# Mk3_Prototype3.net
KiCad netlist of a schematic drawn in EAGLE
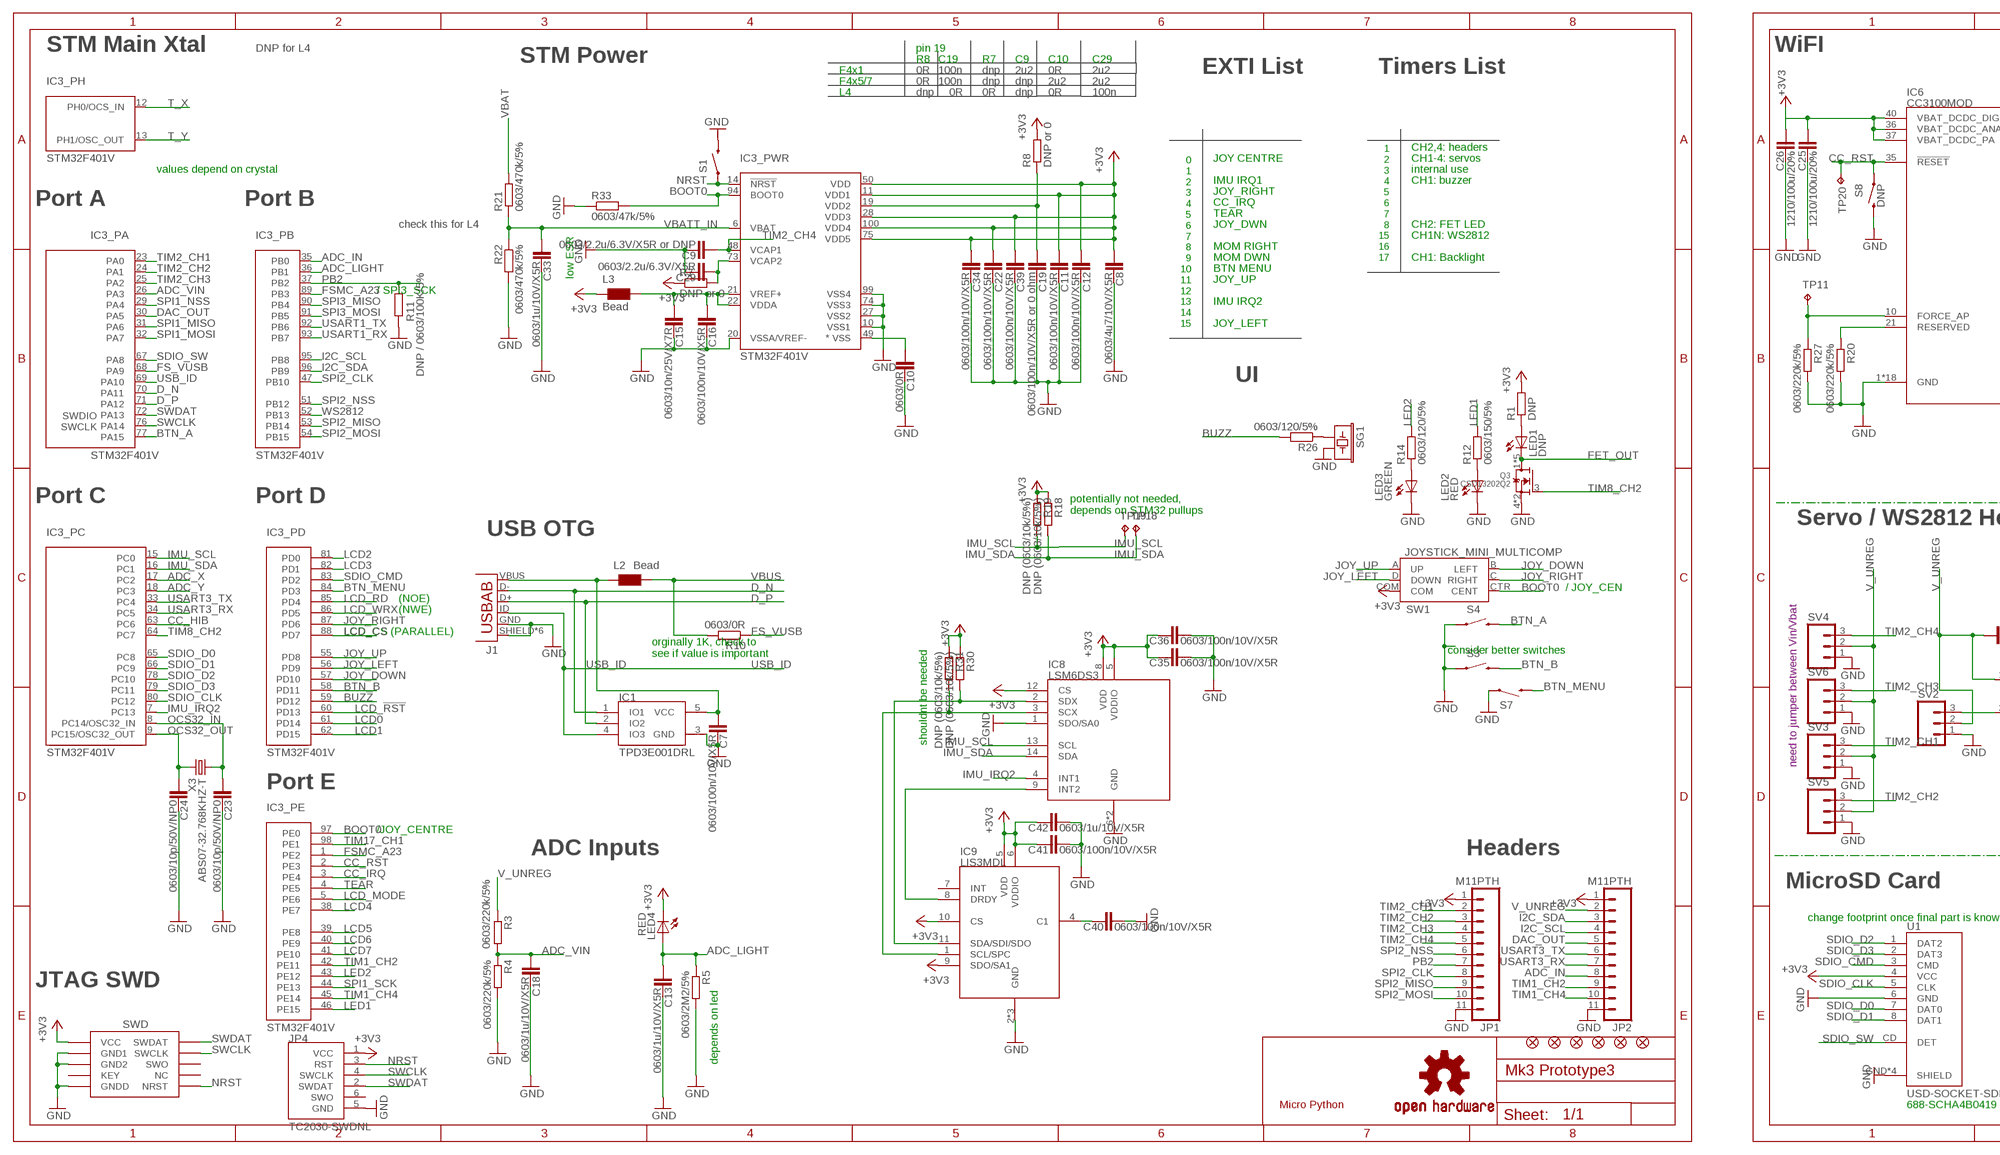
[diagram p0: schematic, sheet 1, part 1 of 2]
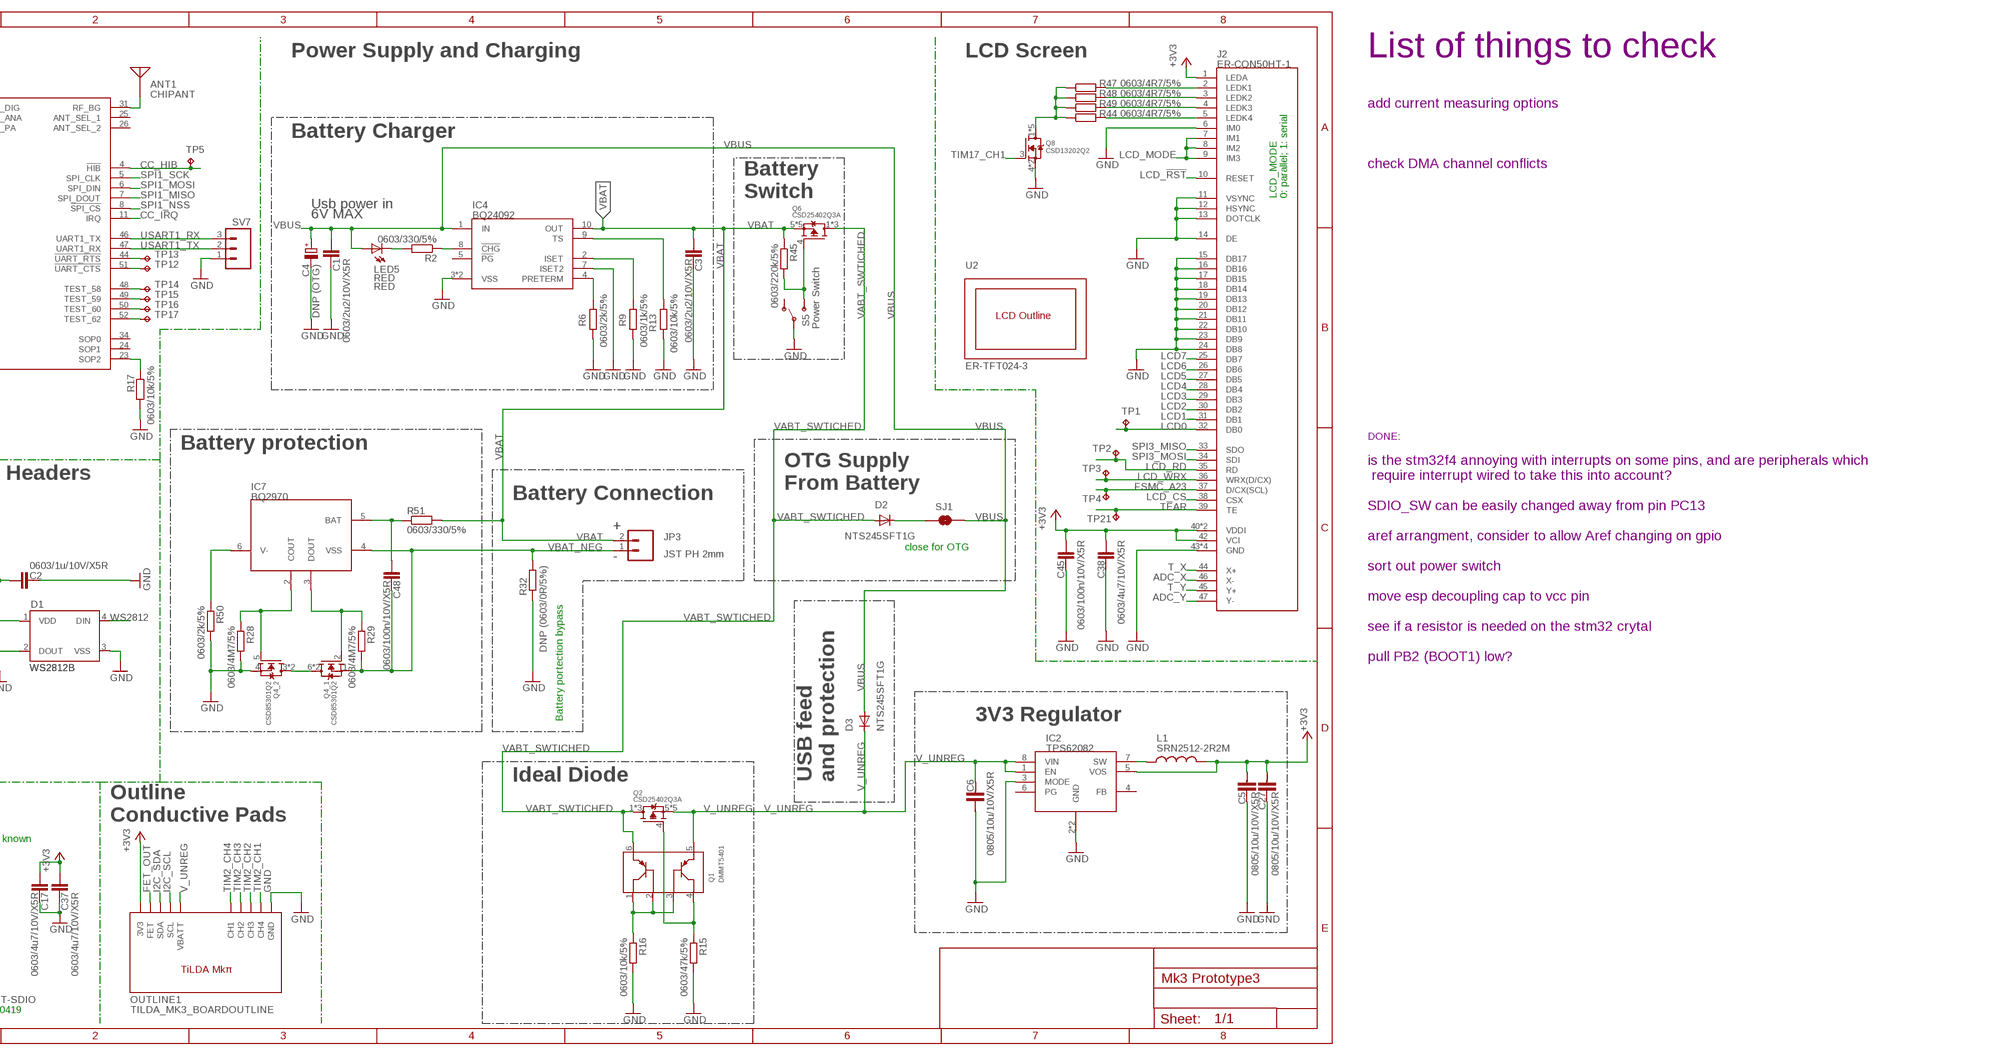
[diagram p1: schematic, sheet 1, part 2 of 2]

(export (version "E")
  (design (tool "Eeschema 10.0.6"))
  (components
    (comp (ref "ANT1")
      (value "CHIPANT")
      (footprint "eagle-import:2450AT42A100")
      (libsource (lib "eagle-import") (part "CHIPANT"))
    )
    (comp (ref "C1")
      (value "0603/2u2/10V/X5R")
      (footprint "eagle-import:C0603K-SMALL")
      (libsource (lib "eagle-import") (part "C-EUC0603K-SMALL"))
    )
    (comp (ref "C2")
      (value "0603/1u/10V/X5R")
      (footprint "eagle-import:C0603K-SMALL")
      (libsource (lib "eagle-import") (part "C-EUC0603K-SMALL"))
    )
    (comp (ref "C3")
      (value "0603/2u2/10V/X5R")
      (footprint "eagle-import:C0603K-SMALL")
      (libsource (lib "eagle-import") (part "C-EUC0603K-SMALL"))
    )
    (comp (ref "C4")
      (value "DNP (OTG)")
      (footprint "eagle-import:E2,5-6")
      (libsource (lib "eagle-import") (part "CPOL-EUE2.5-6"))
    )
    (comp (ref "C5")
      (value "0805/10u/10V/X5R")
      (footprint "eagle-import:C0805-N")
      (libsource (lib "eagle-import") (part "CAPACITOR0805-N"))
    )
    (comp (ref "C6")
      (value "0805/10u/10V/X5R")
      (footprint "eagle-import:C0805-N")
      (libsource (lib "eagle-import") (part "CAPACITOR0805-N"))
    )
    (comp (ref "C7")
      (value "0603/100n/10V/X5R")
      (footprint "eagle-import:C0603K-SMALL")
      (libsource (lib "eagle-import") (part "C-EUC0603K-SMALL"))
    )
    (comp (ref "C8")
      (value "0603/4u7/10V/X5R")
      (footprint "eagle-import:C0603K-SMALL")
      (libsource (lib "eagle-import") (part "C-EUC0603K-SMALL"))
    )
    (comp (ref "C9")
      (value "0603/2.2u/6.3V/X5R or DNP")
      (footprint "eagle-import:C0603K-SMALL")
      (libsource (lib "eagle-import") (part "C-EUC0603K-SMALL"))
    )
    (comp (ref "C10")
      (value "0603/0R")
      (footprint "eagle-import:C0603K-SMALL")
      (libsource (lib "eagle-import") (part "C-EUC0603K-SMALL"))
    )
    (comp (ref "C11")
      (value "0603/100n/10V/X5R")
      (footprint "eagle-import:C0603K-SMALL")
      (libsource (lib "eagle-import") (part "C-EUC0603K-SMALL"))
    )
    (comp (ref "C12")
      (value "0603/100n/10V/X5R")
      (footprint "eagle-import:C0603K-SMALL")
      (libsource (lib "eagle-import") (part "C-EUC0603K-SMALL"))
    )
    (comp (ref "C13")
      (value "0603/1u/10V/X5R")
      (footprint "eagle-import:C0603K-SMALL")
      (libsource (lib "eagle-import") (part "C-EUC0603K-SMALL"))
    )
    (comp (ref "C15")
      (value "0603/10n/25V/X7R")
      (footprint "eagle-import:C0603K-SMALL")
      (libsource (lib "eagle-import") (part "C-EUC0603K-SMALL"))
    )
    (comp (ref "C16")
      (value "0603/100n/10V/X5R")
      (footprint "eagle-import:C0603K-SMALL")
      (libsource (lib "eagle-import") (part "C-EUC0603K-SMALL"))
    )
    (comp (ref "C17")
      (value "0603/4u7/10V/X5R")
      (footprint "eagle-import:C0603K-SMALL")
      (libsource (lib "eagle-import") (part "C-EUC0603K-SMALL"))
    )
    (comp (ref "C18")
      (value "0603/1u/10V/X5R")
      (footprint "eagle-import:C0603K-SMALL")
      (libsource (lib "eagle-import") (part "C-EUC0603K-SMALL"))
    )
    (comp (ref "C19")
      (value "0603/100n/10V/X5R or 0 ohm")
      (footprint "eagle-import:C0603K-SMALL")
      (libsource (lib "eagle-import") (part "C-EUC0603K-SMALL"))
    )
    (comp (ref "C22")
      (value "0603/100n/10V/X5R")
      (footprint "eagle-import:C0603K-SMALL")
      (libsource (lib "eagle-import") (part "C-EUC0603K-SMALL"))
    )
    (comp (ref "C23")
      (value "0603/10p/50V/NP0")
      (footprint "eagle-import:C0603K-SMALL")
      (libsource (lib "eagle-import") (part "C-EUC0603K-SMALL"))
    )
    (comp (ref "C24")
      (value "0603/10p/50V/NP0")
      (footprint "eagle-import:C0603K-SMALL")
      (libsource (lib "eagle-import") (part "C-EUC0603K-SMALL"))
    )
    (comp (ref "C25")
      (value "1210/100u/20%")
      (footprint "eagle-import:C1210K")
      (libsource (lib "eagle-import") (part "C-EUC1210K"))
    )
    (comp (ref "C26")
      (value "1210/100u/20%")
      (footprint "eagle-import:C1210K")
      (libsource (lib "eagle-import") (part "C-EUC1210K"))
    )
    (comp (ref "C27")
      (value "0805/10u/10V/X5R")
      (footprint "eagle-import:C0805-N")
      (libsource (lib "eagle-import") (part "CAPACITOR0805-N"))
    )
    (comp (ref "C29")
      (value "0603/2.2u/6.3V/X5R")
      (footprint "eagle-import:C0603K-SMALL")
      (libsource (lib "eagle-import") (part "C-EUC0603K-SMALL"))
    )
    (comp (ref "C33")
      (value "0603/1u/10V/X5R")
      (footprint "eagle-import:C0603K-SMALL")
      (libsource (lib "eagle-import") (part "C-EUC0603K-SMALL"))
    )
    (comp (ref "C34")
      (value "0603/100n/10V/X5R")
      (footprint "eagle-import:C0603K-SMALL")
      (libsource (lib "eagle-import") (part "C-EUC0603K-SMALL"))
    )
    (comp (ref "C35")
      (value "0603/100n/10V/X5R")
      (footprint "eagle-import:C0603K-SMALL")
      (libsource (lib "eagle-import") (part "C-EUC0603K-SMALL"))
    )
    (comp (ref "C36")
      (value "0603/100n/10V/X5R")
      (footprint "eagle-import:C0603K-SMALL")
      (libsource (lib "eagle-import") (part "C-EUC0603K-SMALL"))
    )
    (comp (ref "C37")
      (value "0603/4u7/10V/X5R")
      (footprint "eagle-import:C0603K-SMALL")
      (libsource (lib "eagle-import") (part "C-EUC0603K-SMALL"))
    )
    (comp (ref "C38")
      (value "0603/4u7/10V/X5R")
      (footprint "eagle-import:C0603K-SMALL")
      (libsource (lib "eagle-import") (part "C-EUC0603K-SMALL"))
    )
    (comp (ref "C39")
      (value "0603/100n/10V/X5R")
      (footprint "eagle-import:C0603K-SMALL")
      (libsource (lib "eagle-import") (part "C-EUC0603K-SMALL"))
    )
    (comp (ref "C40")
      (value "0603/100n/10V/X5R")
      (footprint "eagle-import:C0603K-SMALL")
      (libsource (lib "eagle-import") (part "C-EUC0603K-SMALL"))
    )
    (comp (ref "C41")
      (value "0603/100n/10V/X5R")
      (footprint "eagle-import:C0603K-SMALL")
      (libsource (lib "eagle-import") (part "C-EUC0603K-SMALL"))
    )
    (comp (ref "C42")
      (value "0603/1u/10V/X5R")
      (footprint "eagle-import:C0603K-SMALL")
      (libsource (lib "eagle-import") (part "C-EUC0603K-SMALL"))
    )
    (comp (ref "C45")
      (value "0603/100n/10V/X5R")
      (footprint "eagle-import:C0603K-SMALL")
      (libsource (lib "eagle-import") (part "C-EUC0603K-SMALL"))
    )
    (comp (ref "C48")
      (value "0603/100n/10V/X5R")
      (footprint "eagle-import:C0603K-SMALL")
      (libsource (lib "eagle-import") (part "C-EUC0603K-SMALL"))
    )
    (comp (ref "D1")
      (value "WS2812B")
      (footprint "eagle-import:WS2812B")
      (libsource (lib "eagle-import") (part "WS2812B"))
    )
    (comp (ref "D2")
      (value "NTS245SFT1G")
      (footprint "eagle-import:SOD123")
      (libsource (lib "eagle-import") (part "1N4148-SOD123"))
    )
    (comp (ref "D3")
      (value "NTS245SFT1G")
      (footprint "eagle-import:SOD123")
      (libsource (lib "eagle-import") (part "1N4148-SOD123"))
    )
    (comp (ref "FID1")
      (value "FIDUCIAL1X2.5-STOP")
      (footprint "eagle-import:FIDUCIAL-1X2.5-STOP")
      (libsource (lib "eagle-import") (part "FIDUCIAL1X2.5-STOP"))
    )
    (comp (ref "FID2")
      (value "FIDUCIAL1X2.5-STOP")
      (footprint "eagle-import:FIDUCIAL-1X2.5-STOP")
      (libsource (lib "eagle-import") (part "FIDUCIAL1X2.5-STOP"))
    )
    (comp (ref "FID3")
      (value "FIDUCIAL1X2.5-STOP")
      (footprint "eagle-import:FIDUCIAL-1X2.5-STOP")
      (libsource (lib "eagle-import") (part "FIDUCIAL1X2.5-STOP"))
    )
    (comp (ref "FID4")
      (value "FIDUCIAL1X2.5-STOP")
      (footprint "eagle-import:FIDUCIAL-1X2.5-STOP")
      (libsource (lib "eagle-import") (part "FIDUCIAL1X2.5-STOP"))
    )
    (comp (ref "FID5")
      (value "FIDUCIAL1X2.5-STOP")
      (footprint "eagle-import:FIDUCIAL-1X2.5-STOP")
      (libsource (lib "eagle-import") (part "FIDUCIAL1X2.5-STOP"))
    )
    (comp (ref "FID6")
      (value "FIDUCIAL1X2.5-STOP")
      (footprint "eagle-import:FIDUCIAL-1X2.5-STOP")
      (libsource (lib "eagle-import") (part "FIDUCIAL1X2.5-STOP"))
    )
    (comp (ref "IC1")
      (value "TPD3E001DRL")
      (footprint "eagle-import:DRL-5")
      (libsource (lib "eagle-import") (part "TPD3E001DRL"))
    )
    (comp (ref "IC2")
      (value "TPS62082")
      (footprint "eagle-import:WSON8")
      (libsource (lib "eagle-import") (part "TPS62082"))
    )
    (comp (ref "IC3")
      (value "STM32F401V")
      (footprint "eagle-import:TQFP100")
      (fields (field (name "FARNELL") "2432116"))
      (libsource (lib "eagle-import") (part "STM32F401V"))
    )
    (comp (ref "IC4")
      (value "BQ24092")
      (footprint "eagle-import:HVSSOP10")
      (libsource (lib "eagle-import") (part "BQ2409X"))
    )
    (comp (ref "IC6")
      (value "CC3100MOD")
      (footprint "eagle-import:CC3100MOD")
      (libsource (lib "eagle-import") (part "CC3100MOD"))
    )
    (comp (ref "IC7")
      (value "BQ2970")
      (footprint "eagle-import:WSON-6")
      (libsource (lib "eagle-import") (part "BQ2970"))
    )
    (comp (ref "IC8")
      (value "LSM6DS3")
      (footprint "eagle-import:LGA14")
      (libsource (lib "eagle-import") (part "LSM6DS3"))
    )
    (comp (ref "IC9")
      (value "LIS3MDL")
      (footprint "eagle-import:LGA12")
      (libsource (lib "eagle-import") (part "LIS3MDL"))
    )
    (comp (ref "J1")
      (value "ZX62-AB-5PA(11)")
      (footprint "eagle-import:USB-AB-MICRO-SMD_LWK")
      (libsource (lib "eagle-import") (part "USB-AB-LWK"))
    )
    (comp (ref "J2")
      (value "ER-CON50HT-1")
      (footprint "eagle-import:FH12-50S-0.5SH")
      (libsource (lib "eagle-import") (part "ER-TFT024-3"))
    )
    (comp (ref "J3")
      (value "SWD_SHROUD-PINHEAD")
      (footprint "eagle-import:PINHEAD_2X05_127")
      (libsource (lib "eagle-import") (part "SWD_SHROUD-PINHEAD"))
    )
    (comp (ref "JP1")
      (value "M11PTH")
      (footprint "eagle-import:1X11")
      (libsource (lib "eagle-import") (part "M11PTH"))
    )
    (comp (ref "JP2")
      (value "M11PTH")
      (footprint "eagle-import:1X11")
      (libsource (lib "eagle-import") (part "M11PTH"))
    )
    (comp (ref "JP3")
      (value "JST PH 2mm")
      (footprint "eagle-import:JST-2-SMD")
      (libsource (lib "eagle-import") (part "M02-JST-2MM-SMT"))
    )
    (comp (ref "JP4")
      (value "TC2030-SWDNL")
      (footprint "eagle-import:TC2030-MCP-NL")
      (libsource (lib "eagle-import") (part "TC2030-SWDNL"))
    )
    (comp (ref "L1")
      (value "SRN2512-2R2M")
      (footprint "eagle-import:1008")
      (libsource (lib "eagle-import") (part "INDUCTOR1008"))
    )
    (comp (ref "L2")
      (value "Bead")
      (footprint "eagle-import:WUERTH-0805")
      (libsource (lib "eagle-import") (part "WE-CBF_0805"))
    )
    (comp (ref "L3")
      (value "Bead")
      (footprint "eagle-import:WUERTH-0805")
      (libsource (lib "eagle-import") (part "WE-CBF_0805"))
    )
    (comp (ref "LED1")
      (value "DNP")
      (footprint "eagle-import:LED5MM")
      (libsource (lib "eagle-import") (part "LED5MM"))
    )
    (comp (ref "LED2")
      (value "RED")
      (footprint "eagle-import:LED-0603-CORRECT")
      (fields (field (name "COLOUR") "RED"))
      (libsource (lib "eagle-import") (part "LED0603-CORRECT"))
    )
    (comp (ref "LED3")
      (value "GREEN")
      (footprint "eagle-import:LED-0603-CORRECT")
      (fields (field (name "COLOUR") "GREEN"))
      (libsource (lib "eagle-import") (part "LED0603-CORRECT"))
    )
    (comp (ref "LED4")
      (value "RED")
      (footprint "eagle-import:LED-0603-CORRECT")
      (libsource (lib "eagle-import") (part "LED0603-CORRECT"))
    )
    (comp (ref "LED5")
      (value "RED")
      (footprint "eagle-import:LED-0603-CORRECT")
      (fields (field (name "COLOUR") "RED"))
      (libsource (lib "eagle-import") (part "LED0603-CORRECT"))
    )
    (comp (ref "LOGO1")
      (value "OSHW-LOGOM")
      (footprint "eagle-import:OSHW-LOGO-M")
      (libsource (lib "eagle-import") (part "OSHW-LOGOM"))
    )
    (comp (ref "LOGO3")
      (value "MICROPYTHON-STOP")
      (footprint "eagle-import:UPYTHON_LOGO_STOPONLY")
      (libsource (lib "eagle-import") (part "MICROPYTHON-STOP"))
    )
    (comp (ref "OUTLINE1")
      (value "TILDA_MK3_BOARDOUTLINE")
      (footprint "eagle-import:TILDA_MKE_OUTLINE")
      (libsource (lib "eagle-import") (part "TILDA_MK3_BOARDOUTLINE"))
    )
    (comp (ref "Q1")
      (value "DMMT5401")
      (footprint "eagle-import:SOT26")
      (libsource (lib "eagle-import") (part "DMMT5401"))
    )
    (comp (ref "Q2")
      (value "CSD25402Q3A")
      (footprint "eagle-import:Q3A")
      (libsource (lib "eagle-import") (part "CSD25402Q3A"))
    )
    (comp (ref "Q3")
      (value "CSD13202Q2")
      (footprint "eagle-import:Q2")
      (libsource (lib "eagle-import") (part "CSD13202Q2"))
    )
    (comp (ref "Q4")
      (value "CSD85301Q2")
      (footprint "eagle-import:Q2_DUAL")
      (fields (field (name "FARNELL") "2470183"))
      (libsource (lib "eagle-import") (part "CSD85301Q2"))
    )
    (comp (ref "Q6")
      (value "CSD25402Q3A")
      (footprint "eagle-import:Q3A")
      (libsource (lib "eagle-import") (part "CSD25402Q3A"))
    )
    (comp (ref "Q8")
      (value "CSD13202Q2")
      (footprint "eagle-import:Q2")
      (libsource (lib "eagle-import") (part "CSD13202Q2"))
    )
    (comp (ref "R1")
      (value "DNP")
      (footprint "eagle-import:0207_10")
      (libsource (lib "eagle-import") (part "R-EU_0207/10"))
    )
    (comp (ref "R2")
      (value "0603/330/5%")
      (footprint "eagle-import:C0603K-SMALL")
      (libsource (lib "eagle-import") (part "R-EU_0603K-SMALL"))
    )
    (comp (ref "R3")
      (value "0603/220k/5%")
      (footprint "eagle-import:C0603K-SMALL")
      (libsource (lib "eagle-import") (part "R-EU_0603K-SMALL"))
    )
    (comp (ref "R4")
      (value "0603/220k/5%")
      (footprint "eagle-import:C0603K-SMALL")
      (libsource (lib "eagle-import") (part "R-EU_0603K-SMALL"))
    )
    (comp (ref "R5")
      (value "0603/2M2/5%")
      (footprint "eagle-import:C0603K-SMALL")
      (libsource (lib "eagle-import") (part "R-EU_0603K-SMALL"))
    )
    (comp (ref "R6")
      (value "0603/2k/5%")
      (footprint "eagle-import:C0603K-SMALL")
      (libsource (lib "eagle-import") (part "R-EU_0603K-SMALL"))
    )
    (comp (ref "R7")
      (value "DNP or 0")
      (footprint "eagle-import:C0603K-SMALL")
      (libsource (lib "eagle-import") (part "R-EU_0603K-SMALL"))
    )
    (comp (ref "R8")
      (value "DNP or 0")
      (footprint "eagle-import:C0603K-SMALL")
      (libsource (lib "eagle-import") (part "R-EU_0603K-SMALL"))
    )
    (comp (ref "R9")
      (value "0603/1k/5%")
      (footprint "eagle-import:C0603K-SMALL")
      (libsource (lib "eagle-import") (part "R-EU_0603K-SMALL"))
    )
    (comp (ref "R10")
      (value "0603/0R")
      (footprint "eagle-import:C0603K-SMALL")
      (libsource (lib "eagle-import") (part "R-EU_0603K-SMALL"))
    )
    (comp (ref "R11")
      (value "DNP / 0603/100K/5%")
      (footprint "eagle-import:C0603K-SMALL")
      (libsource (lib "eagle-import") (part "R-EU_0603K-SMALL"))
    )
    (comp (ref "R12")
      (value "0603/150/5%")
      (footprint "eagle-import:C0603K-SMALL")
      (libsource (lib "eagle-import") (part "R-EU_0603K-SMALL"))
    )
    (comp (ref "R13")
      (value "0603/10k/5%")
      (footprint "eagle-import:C0603K-SMALL")
      (libsource (lib "eagle-import") (part "R-EU_0603K-SMALL"))
    )
    (comp (ref "R14")
      (value "0603/120/5%")
      (footprint "eagle-import:C0603K-SMALL")
      (libsource (lib "eagle-import") (part "R-EU_0603K-SMALL"))
    )
    (comp (ref "R15")
      (value "0603/47k/5%")
      (footprint "eagle-import:C0603K-SMALL")
      (libsource (lib "eagle-import") (part "R-EU_0603K-SMALL"))
    )
    (comp (ref "R16")
      (value "0603/10k/5%")
      (footprint "eagle-import:C0603K-SMALL")
      (libsource (lib "eagle-import") (part "R-EU_0603K-SMALL"))
    )
    (comp (ref "R17")
      (value "0603/10k/5%")
      (footprint "eagle-import:C0603K-SMALL")
      (libsource (lib "eagle-import") (part "R-EU_0603K-SMALL"))
    )
    (comp (ref "R18")
      (value "DNP (0603/10k/5%)")
      (footprint "eagle-import:C0603K-SMALL")
      (libsource (lib "eagle-import") (part "R-EU_0603K-SMALL"))
    )
    (comp (ref "R19")
      (value "DNP (0603/10k/5%)")
      (footprint "eagle-import:C0603K-SMALL")
      (libsource (lib "eagle-import") (part "R-EU_0603K-SMALL"))
    )
    (comp (ref "R20")
      (value "0603/220k/5%")
      (footprint "eagle-import:C0603K-SMALL")
      (libsource (lib "eagle-import") (part "R-EU_0603K-SMALL"))
    )
    (comp (ref "R21")
      (value "0603/470k/5%")
      (footprint "eagle-import:C0603K-SMALL")
      (libsource (lib "eagle-import") (part "R-EU_0603K-SMALL"))
    )
    (comp (ref "R22")
      (value "0603/470k/5%")
      (footprint "eagle-import:C0603K-SMALL")
      (libsource (lib "eagle-import") (part "R-EU_0603K-SMALL"))
    )
    (comp (ref "R26")
      (value "0603/120/5%")
      (footprint "eagle-import:C0603K-SMALL")
      (libsource (lib "eagle-import") (part "R-EU_0603K-SMALL"))
    )
    (comp (ref "R27")
      (value "0603/220k/5%")
      (footprint "eagle-import:C0603K-SMALL")
      (libsource (lib "eagle-import") (part "R-EU_0603K-SMALL"))
    )
    (comp (ref "R28")
      (value "0603/4M7/5%")
      (footprint "eagle-import:C0603K-SMALL")
      (libsource (lib "eagle-import") (part "R-EU_0603K-SMALL"))
    )
    (comp (ref "R29")
      (value "0603/4M7/5%")
      (footprint "eagle-import:C0603K-SMALL")
      (libsource (lib "eagle-import") (part "R-EU_0603K-SMALL"))
    )
    (comp (ref "R30")
      (value "DNP (0603/10k/5%)")
      (footprint "eagle-import:C0603K-SMALL")
      (libsource (lib "eagle-import") (part "R-EU_0603K-SMALL"))
    )
    (comp (ref "R31")
      (value "DNP (0603/10k/5%)")
      (footprint "eagle-import:C0603K-SMALL")
      (libsource (lib "eagle-import") (part "R-EU_0603K-SMALL"))
    )
    (comp (ref "R32")
      (value "DNP (0603/0R/5%)")
      (footprint "eagle-import:C0603K-SMALL")
      (libsource (lib "eagle-import") (part "R-EU_0603K-SMALL"))
    )
    (comp (ref "R33")
      (value "0603/47k/5%")
      (footprint "eagle-import:C0603K-SMALL")
      (libsource (lib "eagle-import") (part "R-EU_0603K-SMALL"))
    )
    (comp (ref "R44")
      (value "0603/4R7/5%")
      (footprint "eagle-import:C0603K-SMALL")
      (libsource (lib "eagle-import") (part "R-EU_0603K-SMALL"))
    )
    (comp (ref "R45")
      (value "0603/220k/5%")
      (footprint "eagle-import:C0603K-SMALL")
      (libsource (lib "eagle-import") (part "R-EU_0603K-SMALL"))
    )
    (comp (ref "R47")
      (value "0603/4R7/5%")
      (footprint "eagle-import:C0603K-SMALL")
      (libsource (lib "eagle-import") (part "R-EU_0603K-SMALL"))
    )
    (comp (ref "R48")
      (value "0603/4R7/5%")
      (footprint "eagle-import:C0603K-SMALL")
      (libsource (lib "eagle-import") (part "R-EU_0603K-SMALL"))
    )
    (comp (ref "R49")
      (value "0603/4R7/5%")
      (footprint "eagle-import:C0603K-SMALL")
      (libsource (lib "eagle-import") (part "R-EU_0603K-SMALL"))
    )
    (comp (ref "R50")
      (value "0603/2k/5%")
      (footprint "eagle-import:C0603K-SMALL")
      (libsource (lib "eagle-import") (part "R-EU_0603K-SMALL"))
    )
    (comp (ref "R51")
      (value "0603/330/5%")
      (footprint "eagle-import:C0603K-SMALL")
      (libsource (lib "eagle-import") (part "R-EU_0603K-SMALL"))
    )
    (comp (ref "S1")
      (value "SWITCH-MOMENTARY-2SMD-1101NE")
      (footprint "eagle-import:TACTILE-SWITCH-1101NE")
      (libsource (lib "eagle-import") (part "SWITCH-MOMENTARY-2SMD-1101NE"))
    )
    (comp (ref "S3")
      (value "1217769")
      (footprint "eagle-import:SKPMAPE010-COMBINED")
      (libsource (lib "eagle-import") (part "SWITCH-MOMENTARY-2-SKPMAPE010-COMBINED"))
    )
    (comp (ref "S4")
      (value "1217769")
      (footprint "eagle-import:SKPMAPE010-COMBINED")
      (libsource (lib "eagle-import") (part "SWITCH-MOMENTARY-2-SKPMAPE010-COMBINED"))
    )
    (comp (ref "S5")
      (value "Power Switch")
      (footprint "eagle-import:SWITCH-SPST-SMD-A")
      (libsource (lib "eagle-import") (part "SWITCH-SPST-SMD-A"))
    )
    (comp (ref "S7")
      (value "SWITCH-MOMENTARY-2SMD-1101NE")
      (footprint "eagle-import:TACTILE-SWITCH-1101NE")
      (libsource (lib "eagle-import") (part "SWITCH-MOMENTARY-2SMD-1101NE"))
    )
    (comp (ref "S8")
      (value "DNP")
      (footprint "eagle-import:TACTILE-SWITCH-1101NE")
      (libsource (lib "eagle-import") (part "SWITCH-MOMENTARY-2SMD-1101NE"))
    )
    (comp (ref "SG1")
      (value "BUZZER-PKLCS1212E")
      (footprint "eagle-import:BUZZER-PKLCS1212E")
      (libsource (lib "eagle-import") (part "BUZZER-PKLCS1212E"))
    )
    (comp (ref "SJ1")
      (value "JUMPER-PAD-2-NOYES_SILK")
      (footprint "eagle-import:PAD-JUMPER-2-NO_YES_SILK")
      (libsource (lib "eagle-import") (part "JUMPER-PAD-2-NOYES_SILK"))
    )
    (comp (ref "SV2")
      (value "M03PTH")
      (footprint "eagle-import:1X03")
      (libsource (lib "eagle-import") (part "M03PTH"))
    )
    (comp (ref "SV3")
      (value "M03PTH")
      (footprint "eagle-import:1X03")
      (libsource (lib "eagle-import") (part "M03PTH"))
    )
    (comp (ref "SV4")
      (value "M03PTH")
      (footprint "eagle-import:1X03")
      (libsource (lib "eagle-import") (part "M03PTH"))
    )
    (comp (ref "SV5")
      (value "M03PTH")
      (footprint "eagle-import:1X03")
      (libsource (lib "eagle-import") (part "M03PTH"))
    )
    (comp (ref "SV6")
      (value "M03PTH")
      (footprint "eagle-import:1X03")
      (libsource (lib "eagle-import") (part "M03PTH"))
    )
    (comp (ref "SV7")
      (value "M03PTH")
      (footprint "eagle-import:1X03")
      (libsource (lib "eagle-import") (part "M03PTH"))
    )
    (comp (ref "SW1")
      (value "JOYSTICK_MINI_MULTICOMP")
      (footprint "eagle-import:JOYSTICK_MULTICOMP")
      (libsource (lib "eagle-import") (part "JOYSTICK_MINI_MULTICOMP"))
    )
    (comp (ref "TP1")
      (value "TPB1,27")
      (footprint "eagle-import:B1,27")
      (libsource (lib "eagle-import") (part "TPB1,27"))
    )
    (comp (ref "TP2")
      (value "TPB1,27")
      (footprint "eagle-import:B1,27")
      (libsource (lib "eagle-import") (part "TPB1,27"))
    )
    (comp (ref "TP3")
      (value "TPB1,27")
      (footprint "eagle-import:B1,27")
      (libsource (lib "eagle-import") (part "TPB1,27"))
    )
    (comp (ref "TP4")
      (value "TPB1,27")
      (footprint "eagle-import:B1,27")
      (libsource (lib "eagle-import") (part "TPB1,27"))
    )
    (comp (ref "TP5")
      (value "TPB1,27")
      (footprint "eagle-import:B1,27")
      (libsource (lib "eagle-import") (part "TPB1,27"))
    )
    (comp (ref "TP11")
      (value "TPB1,27")
      (footprint "eagle-import:B1,27")
      (libsource (lib "eagle-import") (part "TPB1,27"))
    )
    (comp (ref "TP12")
      (value "TPB1,27")
      (footprint "eagle-import:B1,27")
      (libsource (lib "eagle-import") (part "TPB1,27"))
    )
    (comp (ref "TP13")
      (value "TPB1,27")
      (footprint "eagle-import:B1,27")
      (libsource (lib "eagle-import") (part "TPB1,27"))
    )
    (comp (ref "TP14")
      (value "TPB1,27")
      (footprint "eagle-import:B1,27")
      (libsource (lib "eagle-import") (part "TPB1,27"))
    )
    (comp (ref "TP15")
      (value "TPB1,27")
      (footprint "eagle-import:B1,27")
      (libsource (lib "eagle-import") (part "TPB1,27"))
    )
    (comp (ref "TP16")
      (value "TPB1,27")
      (footprint "eagle-import:B1,27")
      (libsource (lib "eagle-import") (part "TPB1,27"))
    )
    (comp (ref "TP17")
      (value "TPB1,27")
      (footprint "eagle-import:B1,27")
      (libsource (lib "eagle-import") (part "TPB1,27"))
    )
    (comp (ref "TP18")
      (value "TPB1,27")
      (footprint "eagle-import:B1,27")
      (libsource (lib "eagle-import") (part "TPB1,27"))
    )
    (comp (ref "TP19")
      (value "TPB1,27")
      (footprint "eagle-import:B1,27")
      (libsource (lib "eagle-import") (part "TPB1,27"))
    )
    (comp (ref "TP20")
      (value "TPB1,27")
      (footprint "eagle-import:B1,27")
      (libsource (lib "eagle-import") (part "TPB1,27"))
    )
    (comp (ref "TP21")
      (value "TPB1,27")
      (footprint "eagle-import:B1,27")
      (libsource (lib "eagle-import") (part "TPB1,27"))
    )
    (comp (ref "U1")
      (value "USD-SOCKET-SDIO")
      (footprint "eagle-import:0011XAAX09X")
      (libsource (lib "eagle-import") (part "USD-SOCKET-SDIO"))
    )
    (comp (ref "U2")
      (value "ER-TFT024-3")
      (footprint "eagle-import:ER-TFT024-3")
      (libsource (lib "eagle-import") (part "ER-TFT024-3-OUTLINE"))
    )
    (comp (ref "X3")
      (value "ABS07-32.768KHZ-T")
      (footprint "eagle-import:RESONATOR_EPSON_FC_145")
      (libsource (lib "eagle-import") (part "RESONATOR_EPSON_FC_145"))
    )
  )
  (nets
    (net (code "1") (name "+3V3") (class "Default")
      (node (ref "C11") (pin "2") (pinfunction "2_2") (pintype "passive"))
      (node (ref "C12") (pin "2") (pinfunction "2_2") (pintype "passive"))
      (node (ref "C17") (pin "2") (pinfunction "2_2") (pintype "passive"))
      (node (ref "C22") (pin "2") (pinfunction "2_2") (pintype "passive"))
      (node (ref "C25") (pin "1") (pinfunction "1_1") (pintype "passive"))
      (node (ref "C26") (pin "1") (pinfunction "1_1") (pintype "passive"))
      (node (ref "C27") (pin "1") (pinfunction "1_1") (pintype "passive"))
      (node (ref "C34") (pin "2") (pinfunction "2_2") (pintype "passive"))
      (node (ref "C35") (pin "1") (pinfunction "1_1") (pintype "passive"))
      (node (ref "C36") (pin "1") (pinfunction "1_1") (pintype "passive"))
      (node (ref "C37") (pin "2") (pinfunction "2_2") (pintype "passive"))
      (node (ref "C38") (pin "2") (pinfunction "2_2") (pintype "passive"))
      (node (ref "C39") (pin "2") (pinfunction "2_2") (pintype "passive"))
      (node (ref "C41") (pin "1") (pinfunction "1_1") (pintype "passive"))
      (node (ref "C42") (pin "1") (pinfunction "1_1") (pintype "passive"))
      (node (ref "C45") (pin "2") (pinfunction "2_2") (pintype "passive"))
      (node (ref "C5") (pin "1") (pinfunction "1_1") (pintype "passive"))
      (node (ref "C8") (pin "2") (pinfunction "2_2") (pintype "passive"))
      (node (ref "IC2") (pin "5") (pinfunction "VOS_5") (pintype "input"))
      (node (ref "IC3") (pin "100") (pinfunction "VDD4_100") (pintype "bidirectional"))
      (node (ref "IC3") (pin "11") (pinfunction "VDD1_11") (pintype "bidirectional"))
      (node (ref "IC3") (pin "28") (pinfunction "VDD3_28") (pintype "bidirectional"))
      (node (ref "IC3") (pin "50") (pinfunction "VDD_50") (pintype "bidirectional"))
      (node (ref "IC3") (pin "75") (pinfunction "VDD5_75") (pintype "bidirectional"))
      (node (ref "IC6") (pin "36") (pinfunction "VBAT_DCDC_ANA_36") (pintype "power_in"))
      (node (ref "IC6") (pin "37") (pinfunction "VBAT_DCDC_PA_37") (pintype "power_in"))
      (node (ref "IC6") (pin "40") (pinfunction "VBAT_DCDC_DIG_40") (pintype "power_in"))
      (node (ref "IC8") (pin "12") (pinfunction "CS_12") (pintype "input"))
      (node (ref "IC8") (pin "5") (pinfunction "VDDIO_5") (pintype "power_in"))
      (node (ref "IC8") (pin "8") (pinfunction "VDD_8") (pintype "power_in"))
      (node (ref "IC9") (pin "10") (pinfunction "CS_10") (pintype "input"))
      (node (ref "IC9") (pin "5") (pinfunction "VDD_5") (pintype "power_in"))
      (node (ref "IC9") (pin "6") (pinfunction "VDDIO_6") (pintype "power_in"))
      (node (ref "IC9") (pin "9") (pinfunction "SDO/SA1_9") (pintype "bidirectional"))
      (node (ref "J2") (pin "1") (pinfunction "LEDA_1") (pintype "passive"))
      (node (ref "J2") (pin "40") (pinfunction "VDDI_40") (pintype "power_in"))
      (node (ref "J2") (pin "41") (pinfunction "VDDI_41") (pintype "power_in"))
      (node (ref "J2") (pin "42") (pinfunction "VCI_42") (pintype "power_in"))
      (node (ref "J3") (pin "1") (pinfunction "VCC_1") (pintype "power_in"))
      (node (ref "JP1") (pin "1") (pinfunction "1_1") (pintype "passive"))
      (node (ref "JP2") (pin "1") (pinfunction "1_1") (pintype "passive"))
      (node (ref "JP4") (pin "1") (pinfunction "VCC_1") (pintype "power_in"))
      (node (ref "L1") (pin "2") (pinfunction "2_2") (pintype "passive"))
      (node (ref "L3") (pin "1") (pinfunction "1_1") (pintype "passive"))
      (node (ref "LED4") (pin "C") (pinfunction "C_C") (pintype "passive"))
      (node (ref "OUTLINE1") (pin "3V3") (pinfunction "3V3_3V3") (pintype "bidirectional"))
      (node (ref "R1") (pin "2") (pinfunction "2_2") (pintype "passive"))
      (node (ref "R18") (pin "1") (pinfunction "1_1") (pintype "passive"))
      (node (ref "R19") (pin "1") (pinfunction "1_1") (pintype "passive"))
      (node (ref "R30") (pin "1") (pinfunction "1_1") (pintype "passive"))
      (node (ref "R31") (pin "1") (pinfunction "1_1") (pintype "passive"))
      (node (ref "R7") (pin "1") (pinfunction "1_1") (pintype "passive"))
      (node (ref "R8") (pin "2") (pinfunction "2_2") (pintype "passive"))
      (node (ref "SW1") (pin "COM") (pinfunction "COM_COM") (pintype "bidirectional"))
      (node (ref "U1") (pin "4") (pinfunction "VCC_4") (pintype "bidirectional"))
    )
    (net (code "2") (name "/ADC_IN") (class "Default")
      (node (ref "IC3") (pin "35") (pinfunction "PB0_35") (pintype "bidirectional"))
      (node (ref "JP2") (pin "8") (pinfunction "8_8") (pintype "passive"))
    )
    (net (code "3") (name "/ADC_LIGHT") (class "Default")
      (node (ref "C13") (pin "2") (pinfunction "2_2") (pintype "passive"))
      (node (ref "IC3") (pin "36") (pinfunction "PB1_36") (pintype "bidirectional"))
      (node (ref "LED4") (pin "A") (pinfunction "A_A") (pintype "passive"))
      (node (ref "R5") (pin "1") (pinfunction "1_1") (pintype "passive"))
    )
    (net (code "4") (name "/ADC_VIN") (class "Default")
      (node (ref "C18") (pin "2") (pinfunction "2_2") (pintype "passive"))
      (node (ref "IC3") (pin "26") (pinfunction "PA3_26") (pintype "bidirectional"))
      (node (ref "R3") (pin "2") (pinfunction "2_2") (pintype "passive"))
      (node (ref "R4") (pin "1") (pinfunction "1_1") (pintype "passive"))
    )
    (net (code "5") (name "/ADC_X") (class "Default")
      (node (ref "IC3") (pin "17") (pinfunction "PC2_17") (pintype "bidirectional"))
      (node (ref "J2") (pin "46") (pinfunction "X-_46") (pintype "passive"))
    )
    (net (code "6") (name "/ADC_Y") (class "Default")
      (node (ref "IC3") (pin "18") (pinfunction "PC3_18") (pintype "bidirectional"))
      (node (ref "J2") (pin "47") (pinfunction "Y-_47") (pintype "passive"))
    )
    (net (code "7") (name "/BOOT0") (class "Default")
      (node (ref "IC3") (pin "94") (pinfunction "BOOT0_94") (pintype "bidirectional"))
      (node (ref "IC3") (pin "97") (pinfunction "PE0_97") (pintype "bidirectional"))
      (node (ref "R33") (pin "2") (pinfunction "2_2") (pintype "passive"))
      (node (ref "SW1") (pin "CTR") (pinfunction "CENT_CTR") (pintype "bidirectional"))
    )
    (net (code "8") (name "/BTN_A") (class "Default")
      (node (ref "IC3") (pin "77") (pinfunction "PA15_77") (pintype "bidirectional"))
      (node (ref "S4") (pin "2") (pinfunction "2_2") (pintype "passive"))
      (node (ref "S4") (pin "B1") (pinfunction "2_B1") (pintype "passive"))
      (node (ref "S4") (pin "B2") (pinfunction "2_B2") (pintype "passive"))
    )
    (net (code "9") (name "/BTN_B") (class "Default")
      (node (ref "IC3") (pin "58") (pinfunction "PD11_58") (pintype "bidirectional"))
      (node (ref "S3") (pin "2") (pinfunction "2_2") (pintype "passive"))
      (node (ref "S3") (pin "B1") (pinfunction "2_B1") (pintype "passive"))
      (node (ref "S3") (pin "B2") (pinfunction "2_B2") (pintype "passive"))
    )
    (net (code "10") (name "/BTN_MENU") (class "Default")
      (node (ref "IC3") (pin "84") (pinfunction "PD3_84") (pintype "bidirectional"))
      (node (ref "S7") (pin "2") (pinfunction "2_2") (pintype "passive"))
    )
    (net (code "11") (name "/BUZZ") (class "Default")
      (node (ref "IC3") (pin "59") (pinfunction "PD12_59") (pintype "bidirectional"))
      (node (ref "R26") (pin "2") (pinfunction "2_2") (pintype "passive"))
    )
    (net (code "12") (name "/CC_HIB") (class "Default")
      (node (ref "IC3") (pin "63") (pinfunction "PC6_63") (pintype "bidirectional"))
      (node (ref "IC6") (pin "4") (pinfunction "~{HIB}_4") (pintype "input"))
      (node (ref "TP5") (pin "TP") (pinfunction "TP_TP") (pintype "input"))
    )
    (net (code "13") (name "/CC_IRQ") (class "Default")
      (node (ref "IC3") (pin "3") (pinfunction "PE4_3") (pintype "bidirectional"))
      (node (ref "IC6") (pin "11") (pinfunction "IRQ_11") (pintype "output"))
    )
    (net (code "14") (name "/CC_RST") (class "Default")
      (node (ref "IC3") (pin "2") (pinfunction "PE3_2") (pintype "bidirectional"))
      (node (ref "IC6") (pin "35") (pinfunction "~{RESET}_35") (pintype "input"))
      (node (ref "S8") (pin "1") (pinfunction "1_1") (pintype "passive"))
      (node (ref "TP20") (pin "TP") (pinfunction "TP_TP") (pintype "input"))
    )
    (net (code "15") (name "/DAC_OUT") (class "Default")
      (node (ref "IC3") (pin "30") (pinfunction "PA5_30") (pintype "bidirectional"))
      (node (ref "JP2") (pin "5") (pinfunction "5_5") (pintype "passive"))
    )
    (net (code "16") (name "/D_N") (class "Default")
      (node (ref "IC1") (pin "1") (pinfunction "IO1_1") (pintype "bidirectional"))
      (node (ref "IC3") (pin "70") (pinfunction "PA11_70") (pintype "bidirectional"))
      (node (ref "J1") (pin "D-") (pinfunction "D-_D-") (pintype "bidirectional"))
    )
    (net (code "17") (name "/D_P") (class "Default")
      (node (ref "IC1") (pin "2") (pinfunction "IO2_2") (pintype "bidirectional"))
      (node (ref "IC3") (pin "71") (pinfunction "PA12_71") (pintype "bidirectional"))
      (node (ref "J1") (pin "D+") (pinfunction "D+_D+") (pintype "bidirectional"))
    )
    (net (code "18") (name "/FET_OUT") (class "Default")
      (node (ref "LED1") (pin "K") (pinfunction "C_K") (pintype "passive"))
      (node (ref "OUTLINE1") (pin "FET") (pinfunction "FET_FET") (pintype "bidirectional"))
      (node (ref "Q3") (pin "1") (pinfunction "D_1") (pintype "bidirectional"))
      (node (ref "Q3") (pin "2") (pinfunction "D_2") (pintype "bidirectional"))
      (node (ref "Q3") (pin "5") (pinfunction "D_5") (pintype "bidirectional"))
      (node (ref "Q3") (pin "6") (pinfunction "D_6") (pintype "bidirectional"))
      (node (ref "Q3") (pin "EP1") (pinfunction "D_EP1") (pintype "bidirectional"))
    )
    (net (code "20") (name "/FSMC_A23") (class "Default")
      (node (ref "IC3") (pin "1") (pinfunction "PE2_1") (pintype "bidirectional"))
      (node (ref "IC3") (pin "89") (pinfunction "PB3_89") (pintype "bidirectional"))
      (node (ref "J2") (pin "37") (pinfunction "D/CX(SCL)_37") (pintype "input"))
      (node (ref "TP4") (pin "TP") (pinfunction "TP_TP") (pintype "input"))
    )
    (net (code "21") (name "/FS_VUSB") (class "Default")
      (node (ref "IC3") (pin "68") (pinfunction "PA9_68") (pintype "bidirectional"))
      (node (ref "R10") (pin "1") (pinfunction "1_1") (pintype "passive"))
    )
    (net (code "22") (name "/I2C_SCL") (class "Default")
      (node (ref "IC3") (pin "95") (pinfunction "PB8_95") (pintype "bidirectional"))
      (node (ref "JP2") (pin "4") (pinfunction "4_4") (pintype "passive"))
      (node (ref "OUTLINE1") (pin "SCL") (pinfunction "SCL_SCL") (pintype "bidirectional"))
    )
    (net (code "23") (name "/I2C_SDA") (class "Default")
      (node (ref "IC3") (pin "96") (pinfunction "PB9_96") (pintype "bidirectional"))
      (node (ref "JP2") (pin "3") (pinfunction "3_3") (pintype "passive"))
      (node (ref "OUTLINE1") (pin "SDA") (pinfunction "SDA_SDA") (pintype "bidirectional"))
    )
    (net (code "24") (name "/IMU_IRQ2") (class "Default")
      (node (ref "IC3") (pin "7") (pinfunction "PC13_7") (pintype "bidirectional"))
      (node (ref "IC8") (pin "4") (pinfunction "INT1_4") (pintype "output"))
    )
    (net (code "25") (name "/IMU_SCL") (class "Default")
      (node (ref "IC3") (pin "15") (pinfunction "PC0_15") (pintype "bidirectional"))
      (node (ref "IC8") (pin "13") (pinfunction "SCL_13") (pintype "input"))
      (node (ref "R19") (pin "2") (pinfunction "2_2") (pintype "passive"))
      (node (ref "TP19") (pin "TP") (pinfunction "TP_TP") (pintype "input"))
    )
    (net (code "26") (name "/IMU_SDA") (class "Default")
      (node (ref "IC3") (pin "16") (pinfunction "PC1_16") (pintype "bidirectional"))
      (node (ref "IC8") (pin "14") (pinfunction "SDA_14") (pintype "open_collector"))
      (node (ref "R18") (pin "2") (pinfunction "2_2") (pintype "passive"))
      (node (ref "TP18") (pin "TP") (pinfunction "TP_TP") (pintype "input"))
    )
    (net (code "27") (name "/JOY_DOWN") (class "Default")
      (node (ref "IC3") (pin "57") (pinfunction "PD10_57") (pintype "bidirectional"))
      (node (ref "SW1") (pin "B") (pinfunction "LEFT_B") (pintype "bidirectional"))
    )
    (net (code "28") (name "/JOY_LEFT") (class "Default")
      (node (ref "IC3") (pin "56") (pinfunction "PD9_56") (pintype "bidirectional"))
      (node (ref "SW1") (pin "D") (pinfunction "DOWN_D") (pintype "bidirectional"))
    )
    (net (code "29") (name "/JOY_RIGHT") (class "Default")
      (node (ref "IC3") (pin "87") (pinfunction "PD6_87") (pintype "bidirectional"))
      (node (ref "SW1") (pin "C") (pinfunction "RIGHT_C") (pintype "bidirectional"))
    )
    (net (code "30") (name "/JOY_UP") (class "Default")
      (node (ref "IC3") (pin "55") (pinfunction "PD8_55") (pintype "bidirectional"))
      (node (ref "SW1") (pin "A") (pinfunction "UP_A") (pintype "bidirectional"))
    )
    (net (code "31") (name "/LCD0") (class "Default")
      (node (ref "IC3") (pin "61") (pinfunction "PD14_61") (pintype "bidirectional"))
      (node (ref "J2") (pin "32") (pinfunction "DB0_32") (pintype "bidirectional"))
      (node (ref "TP1") (pin "TP") (pinfunction "TP_TP") (pintype "input"))
    )
    (net (code "32") (name "/LCD1") (class "Default")
      (node (ref "IC3") (pin "62") (pinfunction "PD15_62") (pintype "bidirectional"))
      (node (ref "J2") (pin "31") (pinfunction "DB1_31") (pintype "bidirectional"))
    )
    (net (code "33") (name "/LCD2") (class "Default")
      (node (ref "IC3") (pin "81") (pinfunction "PD0_81") (pintype "bidirectional"))
      (node (ref "J2") (pin "30") (pinfunction "DB2_30") (pintype "bidirectional"))
    )
    (net (code "34") (name "/LCD3") (class "Default")
      (node (ref "IC3") (pin "82") (pinfunction "PD1_82") (pintype "bidirectional"))
      (node (ref "J2") (pin "29") (pinfunction "DB3_29") (pintype "bidirectional"))
    )
    (net (code "35") (name "/LCD4") (class "Default")
      (node (ref "IC3") (pin "38") (pinfunction "PE7_38") (pintype "bidirectional"))
      (node (ref "J2") (pin "28") (pinfunction "DB4_28") (pintype "bidirectional"))
    )
    (net (code "36") (name "/LCD5") (class "Default")
      (node (ref "IC3") (pin "39") (pinfunction "PE8_39") (pintype "bidirectional"))
      (node (ref "J2") (pin "27") (pinfunction "DB5_27") (pintype "bidirectional"))
    )
    (net (code "37") (name "/LCD6") (class "Default")
      (node (ref "IC3") (pin "40") (pinfunction "PE9_40") (pintype "bidirectional"))
      (node (ref "J2") (pin "26") (pinfunction "DB6_26") (pintype "bidirectional"))
    )
    (net (code "38") (name "/LCD7") (class "Default")
      (node (ref "IC3") (pin "41") (pinfunction "PE10_41") (pintype "bidirectional"))
      (node (ref "J2") (pin "25") (pinfunction "DB7_25") (pintype "bidirectional"))
    )
    (net (code "39") (name "/LCD_CS") (class "Default")
      (node (ref "IC3") (pin "88") (pinfunction "PD7_88") (pintype "bidirectional"))
      (node (ref "J2") (pin "38") (pinfunction "CSX_38") (pintype "output"))
    )
    (net (code "40") (name "/LCD_MODE") (class "Default")
      (node (ref "IC3") (pin "5") (pinfunction "PE6_5") (pintype "bidirectional"))
      (node (ref "J2") (pin "7") (pinfunction "IM1_7") (pintype "input"))
      (node (ref "J2") (pin "8") (pinfunction "IM2_8") (pintype "input"))
      (node (ref "J2") (pin "9") (pinfunction "IM3_9") (pintype "input"))
    )
    (net (code "41") (name "/LCD_RD") (class "Default")
      (node (ref "IC3") (pin "85") (pinfunction "PD4_85") (pintype "bidirectional"))
      (node (ref "J2") (pin "35") (pinfunction "RD_35") (pintype "input"))
      (node (ref "TP2") (pin "TP") (pinfunction "TP_TP") (pintype "input"))
    )
    (net (code "42") (name "/LCD_WRX") (class "Default")
      (node (ref "IC3") (pin "86") (pinfunction "PD5_86") (pintype "bidirectional"))
      (node (ref "J2") (pin "36") (pinfunction "WRX(D/CX)_36") (pintype "input"))
      (node (ref "TP3") (pin "TP") (pinfunction "TP_TP") (pintype "input"))
    )
    (net (code "43") (name "/LCD_~{RST}") (class "Default")
      (node (ref "IC3") (pin "60") (pinfunction "PD13_60") (pintype "bidirectional"))
      (node (ref "J2") (pin "10") (pinfunction "RESET_10") (pintype "input"))
    )
    (net (code "44") (name "/LED1") (class "Default")
      (node (ref "IC3") (pin "46") (pinfunction "PE15_46") (pintype "bidirectional"))
      (node (ref "R12") (pin "2") (pinfunction "2_2") (pintype "passive"))
    )
    (net (code "45") (name "/LED2") (class "Default")
      (node (ref "IC3") (pin "43") (pinfunction "PE12_43") (pintype "bidirectional"))
      (node (ref "R14") (pin "2") (pinfunction "2_2") (pintype "passive"))
    )
    (net (code "46") (name "/NRST") (class "Default")
      (node (ref "IC3") (pin "14") (pinfunction "~{NRST}_14") (pintype "bidirectional"))
      (node (ref "J3") (pin "10") (pinfunction "NRST_10") (pintype "bidirectional"))
      (node (ref "JP4") (pin "3") (pinfunction "RST_3") (pintype "output"))
      (node (ref "S1") (pin "1") (pinfunction "1_1") (pintype "passive"))
    )
    (net (code "47") (name "/OCS32_IN") (class "Default")
      (node (ref "C23") (pin "2") (pinfunction "2_2") (pintype "passive"))
      (node (ref "IC3") (pin "8") (pinfunction "PC14/OSC32_IN_8") (pintype "bidirectional"))
      (node (ref "X3") (pin "P$1") (pinfunction "1_P$1") (pintype "bidirectional"))
    )
    (net (code "48") (name "/OCS32_OUT") (class "Default")
      (node (ref "C24") (pin "2") (pinfunction "2_2") (pintype "passive"))
      (node (ref "IC3") (pin "9") (pinfunction "PC15/OSC32_OUT_9") (pintype "bidirectional"))
      (node (ref "X3") (pin "P$2") (pinfunction "2_P$2") (pintype "bidirectional"))
    )
    (net (code "49") (name "/PB2") (class "Default")
      (node (ref "IC3") (pin "37") (pinfunction "PB2_37") (pintype "bidirectional"))
      (node (ref "JP1") (pin "7") (pinfunction "7_7") (pintype "passive"))
      (node (ref "R11") (pin "2") (pinfunction "2_2") (pintype "passive"))
    )
    (net (code "50") (name "/SDIO_CLK") (class "Default")
      (node (ref "IC3") (pin "80") (pinfunction "PC12_80") (pintype "bidirectional"))
      (node (ref "U1") (pin "5") (pinfunction "CLK_5") (pintype "bidirectional"))
    )
    (net (code "51") (name "/SDIO_CMD") (class "Default")
      (node (ref "IC3") (pin "83") (pinfunction "PD2_83") (pintype "bidirectional"))
      (node (ref "U1") (pin "3") (pinfunction "CMD_3") (pintype "bidirectional"))
    )
    (net (code "52") (name "/SDIO_D0") (class "Default")
      (node (ref "IC3") (pin "65") (pinfunction "PC8_65") (pintype "bidirectional"))
      (node (ref "U1") (pin "7") (pinfunction "DAT0_7") (pintype "bidirectional"))
    )
    (net (code "53") (name "/SDIO_D1") (class "Default")
      (node (ref "IC3") (pin "66") (pinfunction "PC9_66") (pintype "bidirectional"))
      (node (ref "U1") (pin "8") (pinfunction "DAT1_8") (pintype "bidirectional"))
    )
    (net (code "54") (name "/SDIO_D2") (class "Default")
      (node (ref "IC3") (pin "78") (pinfunction "PC10_78") (pintype "bidirectional"))
      (node (ref "U1") (pin "1") (pinfunction "DAT2_1") (pintype "bidirectional"))
    )
    (net (code "55") (name "/SDIO_D3") (class "Default")
      (node (ref "IC3") (pin "79") (pinfunction "PC11_79") (pintype "bidirectional"))
      (node (ref "U1") (pin "2") (pinfunction "DAT3_2") (pintype "bidirectional"))
    )
    (net (code "56") (name "/SDIO_SW") (class "Default")
      (node (ref "IC3") (pin "67") (pinfunction "PA8_67") (pintype "bidirectional"))
      (node (ref "U1") (pin "CD") (pinfunction "DET_CD") (pintype "bidirectional"))
    )
    (net (code "57") (name "/SPI1_MISO") (class "Default")
      (node (ref "IC3") (pin "31") (pinfunction "PA6_31") (pintype "bidirectional"))
      (node (ref "IC6") (pin "7") (pinfunction "SPI_DOUT_7") (pintype "output"))
    )
    (net (code "58") (name "/SPI1_MOSI") (class "Default")
      (node (ref "IC3") (pin "32") (pinfunction "PA7_32") (pintype "bidirectional"))
      (node (ref "IC6") (pin "6") (pinfunction "SPI_DIN_6") (pintype "input"))
    )
    (net (code "59") (name "/SPI1_NSS") (class "Default")
      (node (ref "IC3") (pin "29") (pinfunction "PA4_29") (pintype "bidirectional"))
      (node (ref "IC6") (pin "8") (pinfunction "~{SPI_CS}_8") (pintype "input"))
    )
    (net (code "60") (name "/SPI1_SCK") (class "Default")
      (node (ref "IC3") (pin "44") (pinfunction "PE13_44") (pintype "bidirectional"))
      (node (ref "IC6") (pin "5") (pinfunction "SPI_CLK_5") (pintype "input"))
    )
    (net (code "61") (name "/SPI2_CLK") (class "Default")
      (node (ref "IC3") (pin "47") (pinfunction "PB10_47") (pintype "bidirectional"))
      (node (ref "JP1") (pin "8") (pinfunction "8_8") (pintype "passive"))
    )
    (net (code "62") (name "/SPI2_MISO") (class "Default")
      (node (ref "IC3") (pin "53") (pinfunction "PB14_53") (pintype "bidirectional"))
      (node (ref "JP1") (pin "9") (pinfunction "9_9") (pintype "passive"))
    )
    (net (code "63") (name "/SPI2_MOSI") (class "Default")
      (node (ref "IC3") (pin "54") (pinfunction "PB15_54") (pintype "bidirectional"))
      (node (ref "JP1") (pin "10") (pinfunction "10_10") (pintype "passive"))
    )
    (net (code "64") (name "/SPI2_NSS") (class "Default")
      (node (ref "IC3") (pin "51") (pinfunction "PB12_51") (pintype "bidirectional"))
      (node (ref "JP1") (pin "6") (pinfunction "6_6") (pintype "passive"))
    )
    (net (code "65") (name "/SPI3_MISO") (class "Default")
      (node (ref "IC3") (pin "90") (pinfunction "PB4_90") (pintype "bidirectional"))
      (node (ref "J2") (pin "33") (pinfunction "SDO_33") (pintype "output"))
    )
    (net (code "66") (name "/SPI3_MOSI") (class "Default")
      (node (ref "IC3") (pin "91") (pinfunction "PB5_91") (pintype "bidirectional"))
      (node (ref "J2") (pin "34") (pinfunction "SDI_34") (pintype "input"))
    )
    (net (code "67") (name "/SWCLK") (class "Default")
      (node (ref "IC3") (pin "76") (pinfunction "PA14_76") (pintype "bidirectional"))
      (node (ref "J3") (pin "4") (pinfunction "SWCLK_4") (pintype "bidirectional"))
      (node (ref "JP4") (pin "4") (pinfunction "SWCLK_4") (pintype "output"))
    )
    (net (code "68") (name "/SWDAT") (class "Default")
      (node (ref "IC3") (pin "72") (pinfunction "PA13_72") (pintype "bidirectional"))
      (node (ref "J3") (pin "2") (pinfunction "SWDAT_2") (pintype "bidirectional"))
      (node (ref "JP4") (pin "2") (pinfunction "SWDAT_2") (pintype "bidirectional"))
    )
    (net (code "69") (name "/TEAR") (class "Default")
      (node (ref "IC3") (pin "4") (pinfunction "PE5_4") (pintype "bidirectional"))
      (node (ref "J2") (pin "39") (pinfunction "TE_39") (pintype "output"))
      (node (ref "TP21") (pin "TP") (pinfunction "TP_TP") (pintype "input"))
    )
    (net (code "70") (name "/TIM1_CH2") (class "Default")
      (node (ref "IC3") (pin "42") (pinfunction "PE11_42") (pintype "bidirectional"))
      (node (ref "JP2") (pin "9") (pinfunction "9_9") (pintype "passive"))
    )
    (net (code "71") (name "/TIM1_CH4") (class "Default")
      (node (ref "IC3") (pin "45") (pinfunction "PE14_45") (pintype "bidirectional"))
      (node (ref "JP2") (pin "10") (pinfunction "10_10") (pintype "passive"))
    )
    (net (code "72") (name "/TIM2_CH1") (class "Default")
      (node (ref "IC3") (pin "23") (pinfunction "PA0_23") (pintype "bidirectional"))
      (node (ref "JP1") (pin "2") (pinfunction "2_2") (pintype "passive"))
      (node (ref "OUTLINE1") (pin "CH4") (pinfunction "CH4_CH4") (pintype "bidirectional"))
      (node (ref "SV3") (pin "3") (pinfunction "3_3") (pintype "passive"))
    )
    (net (code "73") (name "/TIM2_CH2") (class "Default")
      (node (ref "IC3") (pin "24") (pinfunction "PA1_24") (pintype "bidirectional"))
      (node (ref "JP1") (pin "3") (pinfunction "3_3") (pintype "passive"))
      (node (ref "OUTLINE1") (pin "CH3") (pinfunction "CH3_CH3") (pintype "bidirectional"))
      (node (ref "SV5") (pin "3") (pinfunction "3_3") (pintype "passive"))
    )
    (net (code "74") (name "/TIM2_CH3") (class "Default")
      (node (ref "IC3") (pin "25") (pinfunction "PA2_25") (pintype "bidirectional"))
      (node (ref "JP1") (pin "4") (pinfunction "4_4") (pintype "passive"))
      (node (ref "OUTLINE1") (pin "CH2") (pinfunction "CH2_CH2") (pintype "bidirectional"))
      (node (ref "SV6") (pin "3") (pinfunction "3_3") (pintype "passive"))
    )
    (net (code "75") (name "/TIM2_CH4") (class "Default")
      (node (ref "C9") (pin "2") (pinfunction "2_2") (pintype "passive"))
      (node (ref "IC3") (pin "48") (pinfunction "VCAP1_48") (pintype "bidirectional"))
      (node (ref "JP1") (pin "5") (pinfunction "5_5") (pintype "passive"))
      (node (ref "OUTLINE1") (pin "CH1") (pinfunction "CH1_CH1") (pintype "bidirectional"))
      (node (ref "SV4") (pin "3") (pinfunction "3_3") (pintype "passive"))
    )
    (net (code "76") (name "/TIM8_CH2") (class "Default")
      (node (ref "IC3") (pin "64") (pinfunction "PC7_64") (pintype "bidirectional"))
      (node (ref "Q3") (pin "3") (pinfunction "G_3") (pintype "bidirectional"))
    )
    (net (code "77") (name "/TIM17_CH1") (class "Default")
      (node (ref "IC3") (pin "98") (pinfunction "PE1_98") (pintype "bidirectional"))
      (node (ref "Q8") (pin "3") (pinfunction "G_3") (pintype "bidirectional"))
    )
    (net (code "78") (name "/T_X") (class "Default")
      (node (ref "IC3") (pin "12") (pinfunction "PH0/OCS_IN_12") (pintype "bidirectional"))
      (node (ref "J2") (pin "44") (pinfunction "X+_44") (pintype "passive"))
    )
    (net (code "79") (name "/T_Y") (class "Default")
      (node (ref "IC3") (pin "13") (pinfunction "PH1/OSC_OUT_13") (pintype "bidirectional"))
      (node (ref "J2") (pin "45") (pinfunction "Y+_45") (pintype "passive"))
    )
    (net (code "80") (name "/USART1_RX") (class "Default")
      (node (ref "IC3") (pin "93") (pinfunction "PB7_93") (pintype "bidirectional"))
      (node (ref "IC6") (pin "46") (pinfunction "UART1_TX_46") (pintype "output"))
      (node (ref "SV7") (pin "3") (pinfunction "3_3") (pintype "passive"))
    )
    (net (code "81") (name "/USART1_TX") (class "Default")
      (node (ref "IC3") (pin "92") (pinfunction "PB6_92") (pintype "bidirectional"))
      (node (ref "IC6") (pin "47") (pinfunction "UART1_RX_47") (pintype "input"))
      (node (ref "SV7") (pin "2") (pinfunction "2_2") (pintype "passive"))
    )
    (net (code "82") (name "/USART3_RX") (class "Default")
      (node (ref "IC3") (pin "34") (pinfunction "PC5_34") (pintype "bidirectional"))
      (node (ref "JP2") (pin "7") (pinfunction "7_7") (pintype "passive"))
    )
    (net (code "83") (name "/USART3_TX") (class "Default")
      (node (ref "IC3") (pin "33") (pinfunction "PC4_33") (pintype "bidirectional"))
      (node (ref "JP2") (pin "6") (pinfunction "6_6") (pintype "passive"))
    )
    (net (code "84") (name "/USB_ID") (class "Default")
      (node (ref "IC1") (pin "4") (pinfunction "IO3_4") (pintype "bidirectional"))
      (node (ref "IC3") (pin "69") (pinfunction "PA10_69") (pintype "bidirectional"))
      (node (ref "J1") (pin "ID") (pinfunction "USBID_ID") (pintype "bidirectional"))
    )
    (net (code "85") (name "/VABT_SWTICHED") (class "Default")
      (node (ref "D2") (pin "A") (pinfunction "A_A") (pintype "passive"))
      (node (ref "Q1") (pin "6") (pinfunction "E1_6") (pintype "passive"))
      (node (ref "Q2") (pin "1") (pinfunction "D_1") (pintype "bidirectional"))
      (node (ref "Q2") (pin "2") (pinfunction "D_2") (pintype "bidirectional"))
      (node (ref "Q2") (pin "3") (pinfunction "D_3") (pintype "bidirectional"))
      (node (ref "Q6") (pin "1") (pinfunction "D_1") (pintype "bidirectional"))
      (node (ref "Q6") (pin "2") (pinfunction "D_2") (pintype "bidirectional"))
      (node (ref "Q6") (pin "3") (pinfunction "D_3") (pintype "bidirectional"))
    )
    (net (code "86") (name "/VBATT_IN") (class "Default")
      (node (ref "C33") (pin "2") (pinfunction "2_2") (pintype "passive"))
      (node (ref "IC3") (pin "6") (pinfunction "VBAT_6") (pintype "bidirectional"))
      (node (ref "R21") (pin "1") (pinfunction "1_1") (pintype "passive"))
      (node (ref "R22") (pin "1") (pinfunction "1_1") (pintype "passive"))
    )
    (net (code "87") (name "/VBAT_NEG") (class "Default")
      (node (ref "C48") (pin "1") (pinfunction "1_1") (pintype "passive"))
      (node (ref "IC7") (pin "4") (pinfunction "VSS_4") (pintype "power_in"))
      (node (ref "JP3") (pin "1") (pinfunction "1_1") (pintype "passive"))
      (node (ref "Q4") (pin "1") (pinfunction "S_1") (pintype "bidirectional"))
      (node (ref "R29") (pin "2") (pinfunction "2_2") (pintype "passive"))
      (node (ref "R32") (pin "2") (pinfunction "2_2") (pintype "passive"))
    )
    (net (code "88") (name "/VBUS") (class "Default")
      (node (ref "C1") (pin "2") (pinfunction "2_2") (pintype "passive"))
      (node (ref "C4") (pin "+") (pinfunction "+_+") (pintype "passive"))
      (node (ref "D3") (pin "A") (pinfunction "A_A") (pintype "passive"))
      (node (ref "IC4") (pin "1") (pinfunction "IN_1") (pintype "power_in"))
      (node (ref "L2") (pin "2") (pinfunction "2_2") (pintype "passive"))
      (node (ref "LED5") (pin "A") (pinfunction "A_A") (pintype "passive"))
      (node (ref "R10") (pin "2") (pinfunction "2_2") (pintype "passive"))
      (node (ref "SJ1") (pin "2") (pinfunction "2_2") (pintype "passive"))
    )
    (net (code "89") (name "/V_UNREG") (class "Default")
      (node (ref "C2") (pin "2") (pinfunction "2_2") (pintype "passive"))
      (node (ref "C6") (pin "1") (pinfunction "1_1") (pintype "passive"))
      (node (ref "D1") (pin "1") (pinfunction "VDD_1") (pintype "power_in"))
      (node (ref "D3") (pin "C") (pinfunction "C_C") (pintype "passive"))
      (node (ref "IC2") (pin "1") (pinfunction "EN_1") (pintype "input"))
      (node (ref "IC2") (pin "8") (pinfunction "VIN_8") (pintype "power_in"))
      (node (ref "JP2") (pin "2") (pinfunction "2_2") (pintype "passive"))
      (node (ref "OUTLINE1") (pin "VBATT") (pinfunction "VBATT_VBATT") (pintype "bidirectional"))
      (node (ref "Q1") (pin "5") (pinfunction "E2_5") (pintype "passive"))
      (node (ref "Q2") (pin "5") (pinfunction "S_5") (pintype "bidirectional"))
      (node (ref "Q2") (pin "6") (pinfunction "S_6") (pintype "bidirectional"))
      (node (ref "Q2") (pin "7") (pinfunction "S_7") (pintype "bidirectional"))
      (node (ref "Q2") (pin "8") (pinfunction "S_8") (pintype "bidirectional"))
      (node (ref "Q2") (pin "EP") (pinfunction "S_EP") (pintype "bidirectional"))
      (node (ref "R3") (pin "1") (pinfunction "1_1") (pintype "passive"))
      (node (ref "SV2") (pin "2") (pinfunction "2_2") (pintype "passive"))
      (node (ref "SV3") (pin "2") (pinfunction "2_2") (pintype "passive"))
      (node (ref "SV4") (pin "2") (pinfunction "2_2") (pintype "passive"))
      (node (ref "SV5") (pin "2") (pinfunction "2_2") (pintype "passive"))
      (node (ref "SV6") (pin "2") (pinfunction "2_2") (pintype "passive"))
    )
    (net (code "90") (name "/WS2812") (class "Default")
      (node (ref "D1") (pin "4") (pinfunction "DIN_4") (pintype "input"))
      (node (ref "IC3") (pin "52") (pinfunction "PB13_52") (pintype "bidirectional"))
    )
    (net (code "91") (name "GND") (class "Default")
      (node (ref "C1") (pin "1") (pinfunction "1_1") (pintype "passive"))
      (node (ref "C10") (pin "1") (pinfunction "1_1") (pintype "passive"))
      (node (ref "C11") (pin "1") (pinfunction "1_1") (pintype "passive"))
      (node (ref "C12") (pin "1") (pinfunction "1_1") (pintype "passive"))
      (node (ref "C13") (pin "1") (pinfunction "1_1") (pintype "passive"))
      (node (ref "C15") (pin "1") (pinfunction "1_1") (pintype "passive"))
      (node (ref "C16") (pin "1") (pinfunction "1_1") (pintype "passive"))
      (node (ref "C17") (pin "1") (pinfunction "1_1") (pintype "passive"))
      (node (ref "C18") (pin "1") (pinfunction "1_1") (pintype "passive"))
      (node (ref "C19") (pin "1") (pinfunction "1_1") (pintype "passive"))
      (node (ref "C2") (pin "1") (pinfunction "1_1") (pintype "passive"))
      (node (ref "C22") (pin "1") (pinfunction "1_1") (pintype "passive"))
      (node (ref "C23") (pin "1") (pinfunction "1_1") (pintype "passive"))
      (node (ref "C24") (pin "1") (pinfunction "1_1") (pintype "passive"))
      (node (ref "C25") (pin "2") (pinfunction "2_2") (pintype "passive"))
      (node (ref "C26") (pin "2") (pinfunction "2_2") (pintype "passive"))
      (node (ref "C27") (pin "2") (pinfunction "2_2") (pintype "passive"))
      (node (ref "C29") (pin "1") (pinfunction "1_1") (pintype "passive"))
      (node (ref "C3") (pin "1") (pinfunction "1_1") (pintype "passive"))
      (node (ref "C33") (pin "1") (pinfunction "1_1") (pintype "passive"))
      (node (ref "C34") (pin "1") (pinfunction "1_1") (pintype "passive"))
      (node (ref "C35") (pin "2") (pinfunction "2_2") (pintype "passive"))
      (node (ref "C36") (pin "2") (pinfunction "2_2") (pintype "passive"))
      (node (ref "C37") (pin "1") (pinfunction "1_1") (pintype "passive"))
      (node (ref "C38") (pin "1") (pinfunction "1_1") (pintype "passive"))
      (node (ref "C39") (pin "1") (pinfunction "1_1") (pintype "passive"))
      (node (ref "C4") (pin "-") (pinfunction "-_-") (pintype "passive"))
      (node (ref "C40") (pin "2") (pinfunction "2_2") (pintype "passive"))
      (node (ref "C41") (pin "2") (pinfunction "2_2") (pintype "passive"))
      (node (ref "C42") (pin "2") (pinfunction "2_2") (pintype "passive"))
      (node (ref "C45") (pin "1") (pinfunction "1_1") (pintype "passive"))
      (node (ref "C5") (pin "2") (pinfunction "2_2") (pintype "passive"))
      (node (ref "C6") (pin "2") (pinfunction "2_2") (pintype "passive"))
      (node (ref "C7") (pin "1") (pinfunction "1_1") (pintype "passive"))
      (node (ref "C8") (pin "1") (pinfunction "1_1") (pintype "passive"))
      (node (ref "C9") (pin "1") (pinfunction "1_1") (pintype "passive"))
      (node (ref "D1") (pin "3") (pinfunction "VSS_3") (pintype "power_in"))
      (node (ref "IC1") (pin "3") (pinfunction "GND_3") (pintype "power_in"))
      (node (ref "IC2") (pin "2") (pinfunction "GND_2") (pintype "power_in"))
      (node (ref "IC2") (pin "3") (pinfunction "MODE_3") (pintype "input"))
      (node (ref "IC2") (pin "EP") (pinfunction "GND_EP") (pintype "power_in"))
      (node (ref "IC3") (pin "10") (pinfunction "VSS1_10") (pintype "bidirectional"))
      (node (ref "IC3") (pin "20") (pinfunction "VSSA/VREF-_20") (pintype "bidirectional"))
      (node (ref "IC3") (pin "27") (pinfunction "VSS2_27") (pintype "bidirectional"))
      (node (ref "IC3") (pin "74") (pinfunction "VSS3_74") (pintype "bidirectional"))
      (node (ref "IC3") (pin "99") (pinfunction "VSS4_99") (pintype "bidirectional"))
      (node (ref "IC4") (pin "3") (pinfunction "VSS_3") (pintype "power_in"))
      (node (ref "IC4") (pin "7") (pinfunction "ISET2_7") (pintype "input"))
      (node (ref "IC4") (pin "EP") (pinfunction "VSS_EP") (pintype "power_in"))
      (node (ref "IC6") (pin "1") (pinfunction "GND_1") (pintype "power_in"))
      (node (ref "IC6") (pin "16") (pinfunction "GND_16") (pintype "power_in"))
      (node (ref "IC6") (pin "2") (pinfunction "GND_2") (pintype "power_in"))
      (node (ref "IC6") (pin "27") (pinfunction "GND_27") (pintype "power_in"))
      (node (ref "IC6") (pin "28") (pinfunction "GND_28") (pintype "power_in"))
      (node (ref "IC6") (pin "30") (pinfunction "GND_30") (pintype "power_in"))
      (node (ref "IC6") (pin "32") (pinfunction "GND_32") (pintype "power_in"))
      (node (ref "IC6") (pin "38") (pinfunction "GND_38") (pintype "power_in"))
      (node (ref "IC6") (pin "43") (pinfunction "GND_43") (pintype "power_in"))
      (node (ref "IC6") (pin "55") (pinfunction "GND_55") (pintype "power_in"))
      (node (ref "IC6") (pin "56") (pinfunction "GND_56") (pintype "power_in"))
      (node (ref "IC6") (pin "57") (pinfunction "GND_57") (pintype "power_in"))
      (node (ref "IC6") (pin "58") (pinfunction "GND_58") (pintype "power_in"))
      (node (ref "IC6") (pin "59") (pinfunction "GND_59") (pintype "power_in"))
      (node (ref "IC6") (pin "60") (pinfunction "GND_60") (pintype "power_in"))
      (node (ref "IC6") (pin "61") (pinfunction "GND_61") (pintype "power_in"))
      (node (ref "IC6") (pin "62") (pinfunction "GND_62") (pintype "power_in"))
      (node (ref "IC6") (pin "63") (pinfunction "GND_63") (pintype "power_in"))
      (node (ref "IC8") (pin "1") (pinfunction "SDO/SA0_1") (pintype "bidirectional"))
      (node (ref "IC8") (pin "6") (pinfunction "GND_6") (pintype "power_in"))
      (node (ref "IC8") (pin "7") (pinfunction "GND_7") (pintype "power_in"))
      (node (ref "IC9") (pin "12") (pinfunction "GND_12") (pintype "power_in"))
      (node (ref "IC9") (pin "2") (pinfunction "GND_2") (pintype "power_in"))
      (node (ref "IC9") (pin "3") (pinfunction "GND_3") (pintype "power_in"))
      (node (ref "J1") (pin "GND") (pinfunction "GND_GND") (pintype "bidirectional"))
      (node (ref "J1") (pin "SHIELD") (pinfunction "SHIELD_SHIELD") (pintype "bidirectional"))
      (node (ref "J1") (pin "SHIELD@0") (pinfunction "SHIELD_SHIELD@0") (pintype "bidirectional"))
      (node (ref "J1") (pin "SHIELD@1") (pinfunction "SHIELD_SHIELD@1") (pintype "bidirectional"))
      (node (ref "J1") (pin "SHIELD@2") (pinfunction "SHIELD_SHIELD@2") (pintype "bidirectional"))
      (node (ref "J1") (pin "SHIELD@3") (pinfunction "SHIELD_SHIELD@3") (pintype "bidirectional"))
      (node (ref "J1") (pin "SHIELD@5") (pinfunction "SHIELD_SHIELD@5") (pintype "bidirectional"))
      (node (ref "J2") (pin "11") (pinfunction "VSYNC_11") (pintype "bidirectional"))
      (node (ref "J2") (pin "12") (pinfunction "HSYNC_12") (pintype "bidirectional"))
      (node (ref "J2") (pin "13") (pinfunction "DOTCLK_13") (pintype "bidirectional"))
      (node (ref "J2") (pin "14") (pinfunction "DE_14") (pintype "input"))
      (node (ref "J2") (pin "15") (pinfunction "DB17_15") (pintype "bidirectional"))
      (node (ref "J2") (pin "16") (pinfunction "DB16_16") (pintype "bidirectional"))
      (node (ref "J2") (pin "17") (pinfunction "DB15_17") (pintype "bidirectional"))
      (node (ref "J2") (pin "18") (pinfunction "DB14_18") (pintype "bidirectional"))
      (node (ref "J2") (pin "19") (pinfunction "DB13_19") (pintype "bidirectional"))
      (node (ref "J2") (pin "20") (pinfunction "DB12_20") (pintype "bidirectional"))
      (node (ref "J2") (pin "21") (pinfunction "DB11_21") (pintype "bidirectional"))
      (node (ref "J2") (pin "22") (pinfunction "DB10_22") (pintype "bidirectional"))
      (node (ref "J2") (pin "23") (pinfunction "DB9_23") (pintype "bidirectional"))
      (node (ref "J2") (pin "24") (pinfunction "DB8_24") (pintype "bidirectional"))
      (node (ref "J2") (pin "43") (pinfunction "GND_43") (pintype "power_in"))
      (node (ref "J2") (pin "48") (pinfunction "GND_48") (pintype "power_in"))
      (node (ref "J2") (pin "49") (pinfunction "GND_49") (pintype "power_in"))
      (node (ref "J2") (pin "50") (pinfunction "GND_50") (pintype "power_in"))
      (node (ref "J2") (pin "6") (pinfunction "IM0_6") (pintype "input"))
      (node (ref "J3") (pin "3") (pinfunction "GND1_3") (pintype "power_in"))
      (node (ref "J3") (pin "5") (pinfunction "GND2_5") (pintype "power_in"))
      (node (ref "J3") (pin "9") (pinfunction "GNDD_9") (pintype "power_in"))
      (node (ref "JP1") (pin "11") (pinfunction "11_11") (pintype "passive"))
      (node (ref "JP2") (pin "11") (pinfunction "11_11") (pintype "passive"))
      (node (ref "JP4") (pin "5") (pinfunction "GND_5") (pintype "power_in"))
      (node (ref "LED2") (pin "C") (pinfunction "C_C") (pintype "passive"))
      (node (ref "LED3") (pin "C") (pinfunction "C_C") (pintype "passive"))
      (node (ref "OUTLINE1") (pin "GND") (pinfunction "GND_GND") (pintype "bidirectional"))
      (node (ref "Q3") (pin "4") (pinfunction "S_4") (pintype "bidirectional"))
      (node (ref "Q3") (pin "EP2") (pinfunction "S_EP2") (pintype "bidirectional"))
      (node (ref "Q4") (pin "4") (pinfunction "S_4") (pintype "bidirectional"))
      (node (ref "Q8") (pin "4") (pinfunction "S_4") (pintype "bidirectional"))
      (node (ref "Q8") (pin "EP2") (pinfunction "S_EP2") (pintype "bidirectional"))
      (node (ref "R11") (pin "1") (pinfunction "1_1") (pintype "passive"))
      (node (ref "R13") (pin "2") (pinfunction "2_2") (pintype "passive"))
      (node (ref "R15") (pin "2") (pinfunction "2_2") (pintype "passive"))
      (node (ref "R16") (pin "2") (pinfunction "2_2") (pintype "passive"))
      (node (ref "R17") (pin "2") (pinfunction "2_2") (pintype "passive"))
      (node (ref "R20") (pin "2") (pinfunction "2_2") (pintype "passive"))
      (node (ref "R22") (pin "2") (pinfunction "2_2") (pintype "passive"))
      (node (ref "R27") (pin "2") (pinfunction "2_2") (pintype "passive"))
      (node (ref "R28") (pin "2") (pinfunction "2_2") (pintype "passive"))
      (node (ref "R32") (pin "1") (pinfunction "1_1") (pintype "passive"))
      (node (ref "R33") (pin "1") (pinfunction "1_1") (pintype "passive"))
      (node (ref "R4") (pin "2") (pinfunction "2_2") (pintype "passive"))
      (node (ref "R5") (pin "2") (pinfunction "2_2") (pintype "passive"))
      (node (ref "R50") (pin "2") (pinfunction "2_2") (pintype "passive"))
      (node (ref "R6") (pin "2") (pinfunction "2_2") (pintype "passive"))
      (node (ref "R9") (pin "2") (pinfunction "2_2") (pintype "passive"))
      (node (ref "S1") (pin "2") (pinfunction "2_2") (pintype "passive"))
      (node (ref "S3") (pin "1") (pinfunction "1_1") (pintype "passive"))
      (node (ref "S3") (pin "A1") (pinfunction "1_A1") (pintype "passive"))
      (node (ref "S3") (pin "A2") (pinfunction "1_A2") (pintype "passive"))
      (node (ref "S4") (pin "1") (pinfunction "1_1") (pintype "passive"))
      (node (ref "S4") (pin "A1") (pinfunction "1_A1") (pintype "passive"))
      (node (ref "S4") (pin "A2") (pinfunction "1_A2") (pintype "passive"))
      (node (ref "S5") (pin "2") (pinfunction "P_2") (pintype "passive"))
      (node (ref "S7") (pin "1") (pinfunction "1_1") (pintype "passive"))
      (node (ref "S8") (pin "2") (pinfunction "2_2") (pintype "passive"))
      (node (ref "SG1") (pin "P$2") (pinfunction "2_P$2") (pintype "passive"))
      (node (ref "SV2") (pin "1") (pinfunction "1_1") (pintype "passive"))
      (node (ref "SV3") (pin "1") (pinfunction "1_1") (pintype "passive"))
      (node (ref "SV4") (pin "1") (pinfunction "1_1") (pintype "passive"))
      (node (ref "SV5") (pin "1") (pinfunction "1_1") (pintype "passive"))
      (node (ref "SV6") (pin "1") (pinfunction "1_1") (pintype "passive"))
      (node (ref "SV7") (pin "1") (pinfunction "1_1") (pintype "passive"))
      (node (ref "U1") (pin "6") (pinfunction "GND_6") (pintype "bidirectional"))
      (node (ref "U1") (pin "GND") (pinfunction "SHIELD_GND") (pintype "bidirectional"))
      (node (ref "U1") (pin "GND1") (pinfunction "SHIELD_GND1") (pintype "bidirectional"))
      (node (ref "U1") (pin "GND2") (pinfunction "SHIELD_GND2") (pintype "bidirectional"))
      (node (ref "U1") (pin "GND3") (pinfunction "SHIELD_GND3") (pintype "bidirectional"))
    )
    (net (code "92") (name "Net-(ANT1-1)") (class "Default")
      (node (ref "ANT1") (pin "P$1") (pinfunction "1_P$1") (pintype "passive"))
      (node (ref "IC6") (pin "31") (pinfunction "RF_BG_31") (pintype "bidirectional"))
    )
    (net (code "93") (name "Net-(D1-DOUT)") (class "Default")
      (node (ref "D1") (pin "2") (pinfunction "DOUT_2") (pintype "output"))
      (node (ref "SV2") (pin "3") (pinfunction "3_3") (pintype "passive"))
    )
    (net (code "94") (name "Net-(D2-PadC)") (class "Default")
      (node (ref "D2") (pin "C") (pinfunction "C_C") (pintype "passive"))
      (node (ref "SJ1") (pin "1") (pinfunction "1_1") (pintype "passive"))
    )
    (net (code "95") (name "Net-(IC1-VCC)") (class "Default")
      (node (ref "C7") (pin "2") (pinfunction "2_2") (pintype "passive"))
      (node (ref "IC1") (pin "5") (pinfunction "VCC_5") (pintype "power_in"))
      (node (ref "J1") (pin "VBUS") (pinfunction "VBUS_VBUS") (pintype "bidirectional"))
      (node (ref "L2") (pin "1") (pinfunction "1_1") (pintype "passive"))
    )
    (net (code "96") (name "Net-(IC2-SW)") (class "Default")
      (node (ref "IC2") (pin "7") (pinfunction "SW_7") (pintype "output"))
      (node (ref "L1") (pin "1") (pinfunction "1_1") (pintype "passive"))
    )
    (net (code "97") (name "Net-(IC3G-VCAP2)") (class "Default")
      (node (ref "C29") (pin "2") (pinfunction "2_2") (pintype "passive"))
      (node (ref "IC3") (pin "73") (pinfunction "VCAP2_73") (pintype "bidirectional"))
      (node (ref "R7") (pin "2") (pinfunction "2_2") (pintype "passive"))
    )
    (net (code "98") (name "Net-(IC3G-VDD2)") (class "Default")
      (node (ref "C19") (pin "2") (pinfunction "2_2") (pintype "passive"))
      (node (ref "IC3") (pin "19") (pinfunction "VDD2_19") (pintype "bidirectional"))
      (node (ref "R8") (pin "1") (pinfunction "1_1") (pintype "passive"))
    )
    (net (code "99") (name "Net-(IC3G-VDDA)") (class "Default")
      (node (ref "C15") (pin "2") (pinfunction "2_2") (pintype "passive"))
      (node (ref "C16") (pin "2") (pinfunction "2_2") (pintype "passive"))
      (node (ref "IC3") (pin "21") (pinfunction "VREF+_21") (pintype "bidirectional"))
      (node (ref "IC3") (pin "22") (pinfunction "VDDA_22") (pintype "bidirectional"))
      (node (ref "L3") (pin "2") (pinfunction "2_2") (pintype "passive"))
    )
    (net (code "100") (name "Net-(IC3G-VSS)") (class "Default")
      (node (ref "C10") (pin "2") (pinfunction "2_2") (pintype "passive"))
      (node (ref "IC3") (pin "49") (pinfunction "VSS_49") (pintype "bidirectional"))
    )
    (net (code "101") (name "Net-(IC4-ISET)") (class "Default")
      (node (ref "IC4") (pin "2") (pinfunction "ISET_2") (pintype "input"))
      (node (ref "R9") (pin "1") (pinfunction "1_1") (pintype "passive"))
    )
    (net (code "102") (name "Net-(IC4-PRETERM)") (class "Default")
      (node (ref "IC4") (pin "4") (pinfunction "PRETERM_4") (pintype "input"))
      (node (ref "R6") (pin "1") (pinfunction "1_1") (pintype "passive"))
    )
    (net (code "103") (name "Net-(IC4-TS)") (class "Default")
      (node (ref "IC4") (pin "9") (pinfunction "TS_9") (pintype "input"))
      (node (ref "R13") (pin "1") (pinfunction "1_1") (pintype "passive"))
    )
    (net (code "104") (name "Net-(IC4-~{CHG})") (class "Default")
      (node (ref "IC4") (pin "8") (pinfunction "~{CHG}_8") (pintype "output"))
      (node (ref "R2") (pin "1") (pinfunction "1_1") (pintype "passive"))
    )
    (net (code "105") (name "Net-(IC6-FORCE_AP)") (class "Default")
      (node (ref "IC6") (pin "10") (pinfunction "FORCE_AP_10") (pintype "bidirectional"))
      (node (ref "R27") (pin "1") (pinfunction "1_1") (pintype "passive"))
      (node (ref "TP11") (pin "TP") (pinfunction "TP_TP") (pintype "input"))
    )
    (net (code "106") (name "Net-(IC6-RESERVED)") (class "Default")
      (node (ref "IC6") (pin "21") (pinfunction "RESERVED_21") (pintype "input"))
      (node (ref "R20") (pin "1") (pinfunction "1_1") (pintype "passive"))
    )
    (net (code "107") (name "Net-(IC6-SOP2)") (class "Default")
      (node (ref "IC6") (pin "23") (pinfunction "SOP2_23") (pintype "bidirectional"))
      (node (ref "R17") (pin "1") (pinfunction "1_1") (pintype "passive"))
    )
    (net (code "108") (name "Net-(IC6-TEST_58)") (class "Default")
      (node (ref "IC6") (pin "48") (pinfunction "TEST_58_48") (pintype "output"))
      (node (ref "TP14") (pin "TP") (pinfunction "TP_TP") (pintype "input"))
    )
    (net (code "109") (name "Net-(IC6-TEST_59)") (class "Default")
      (node (ref "IC6") (pin "49") (pinfunction "TEST_59_49") (pintype "output"))
      (node (ref "TP15") (pin "TP") (pinfunction "TP_TP") (pintype "input"))
    )
    (net (code "110") (name "Net-(IC6-TEST_60)") (class "Default")
      (node (ref "IC6") (pin "50") (pinfunction "TEST_60_50") (pintype "output"))
      (node (ref "TP16") (pin "TP") (pinfunction "TP_TP") (pintype "input"))
    )
    (net (code "111") (name "Net-(IC6-TEST_62)") (class "Default")
      (node (ref "IC6") (pin "52") (pinfunction "TEST_62_52") (pintype "output"))
      (node (ref "TP17") (pin "TP") (pinfunction "TP_TP") (pintype "input"))
    )
    (net (code "112") (name "Net-(IC6-~{UART_CTS})") (class "Default")
      (node (ref "IC6") (pin "51") (pinfunction "~{UART_CTS}_51") (pintype "bidirectional"))
      (node (ref "TP12") (pin "TP") (pinfunction "TP_TP") (pintype "input"))
    )
    (net (code "113") (name "Net-(IC6-~{UART_RTS})") (class "Default")
      (node (ref "IC6") (pin "44") (pinfunction "~{UART_RTS}_44") (pintype "bidirectional"))
      (node (ref "TP13") (pin "TP") (pinfunction "TP_TP") (pintype "input"))
    )
    (net (code "114") (name "Net-(IC7-BAT)") (class "Default")
      (node (ref "C48") (pin "2") (pinfunction "2_2") (pintype "passive"))
      (node (ref "IC7") (pin "5") (pinfunction "BAT_5") (pintype "input"))
      (node (ref "R51") (pin "1") (pinfunction "1_1") (pintype "passive"))
    )
    (net (code "115") (name "Net-(IC7-COUT)") (class "Default")
      (node (ref "IC7") (pin "2") (pinfunction "COUT_2") (pintype "output"))
      (node (ref "Q4") (pin "5") (pinfunction "G_5") (pintype "bidirectional"))
      (node (ref "R28") (pin "1") (pinfunction "1_1") (pintype "passive"))
    )
    (net (code "116") (name "Net-(IC7-DOUT)") (class "Default")
      (node (ref "IC7") (pin "3") (pinfunction "DOUT_3") (pintype "output"))
      (node (ref "Q4") (pin "2") (pinfunction "G_2") (pintype "bidirectional"))
      (node (ref "R29") (pin "1") (pinfunction "1_1") (pintype "passive"))
    )
    (net (code "117") (name "Net-(IC7-V-)") (class "Default")
      (node (ref "IC7") (pin "6") (pinfunction "V-_6") (pintype "input"))
      (node (ref "R50") (pin "1") (pinfunction "1_1") (pintype "passive"))
    )
    (net (code "118") (name "Net-(IC8-INT2)") (class "Default")
      (node (ref "IC8") (pin "9") (pinfunction "INT2_9") (pintype "output"))
      (node (ref "IC9") (pin "8") (pinfunction "DRDY_8") (pintype "output"))
    )
    (net (code "119") (name "Net-(IC8-SCX)") (class "Default")
      (node (ref "IC8") (pin "3") (pinfunction "SCX_3") (pintype "input"))
      (node (ref "IC9") (pin "1") (pinfunction "SCL/SPC_1") (pintype "input"))
      (node (ref "R31") (pin "2") (pinfunction "2_2") (pintype "passive"))
    )
    (net (code "120") (name "Net-(IC8-SDX)") (class "Default")
      (node (ref "IC8") (pin "2") (pinfunction "SDX_2") (pintype "input"))
      (node (ref "IC9") (pin "11") (pinfunction "SDA/SDI/SDO_11") (pintype "bidirectional"))
      (node (ref "R30") (pin "2") (pinfunction "2_2") (pintype "passive"))
    )
    (net (code "121") (name "Net-(IC9-C1)") (class "Default")
      (node (ref "C40") (pin "1") (pinfunction "1_1") (pintype "passive"))
      (node (ref "IC9") (pin "4") (pinfunction "C1_4") (pintype "bidirectional"))
    )
    (net (code "122") (name "Net-(J2-LEDK1)") (class "Default")
      (node (ref "J2") (pin "2") (pinfunction "LEDK1_2") (pintype "passive"))
      (node (ref "R47") (pin "2") (pinfunction "2_2") (pintype "passive"))
    )
    (net (code "123") (name "Net-(J2-LEDK2)") (class "Default")
      (node (ref "J2") (pin "3") (pinfunction "LEDK2_3") (pintype "passive"))
      (node (ref "R48") (pin "2") (pinfunction "2_2") (pintype "passive"))
    )
    (net (code "124") (name "Net-(J2-LEDK3)") (class "Default")
      (node (ref "J2") (pin "4") (pinfunction "LEDK3_4") (pintype "passive"))
      (node (ref "R49") (pin "2") (pinfunction "2_2") (pintype "passive"))
    )
    (net (code "125") (name "Net-(J2-LEDK4)") (class "Default")
      (node (ref "J2") (pin "5") (pinfunction "LEDK4_5") (pintype "passive"))
      (node (ref "R44") (pin "2") (pinfunction "2_2") (pintype "passive"))
    )
    (net (code "126") (name "Net-(LED1-PadA)") (class "Default")
      (node (ref "LED1") (pin "A") (pinfunction "A_A") (pintype "passive"))
      (node (ref "R1") (pin "1") (pinfunction "1_1") (pintype "passive"))
    )
    (net (code "127") (name "Net-(LED2-PadA)") (class "Default")
      (node (ref "LED2") (pin "A") (pinfunction "A_A") (pintype "passive"))
      (node (ref "R12") (pin "1") (pinfunction "1_1") (pintype "passive"))
    )
    (net (code "128") (name "Net-(LED3-PadA)") (class "Default")
      (node (ref "LED3") (pin "A") (pinfunction "A_A") (pintype "passive"))
      (node (ref "R14") (pin "1") (pinfunction "1_1") (pintype "passive"))
    )
    (net (code "129") (name "Net-(LED5-PadC)") (class "Default")
      (node (ref "LED5") (pin "C") (pinfunction "C_C") (pintype "passive"))
      (node (ref "R2") (pin "2") (pinfunction "2_2") (pintype "passive"))
    )
    (net (code "130") (name "Net-(Q1-B1)") (class "Default")
      (node (ref "Q1") (pin "1") (pinfunction "C1_1") (pintype "passive"))
      (node (ref "Q1") (pin "2") (pinfunction "B1_2") (pintype "passive"))
      (node (ref "Q1") (pin "3") (pinfunction "B2_3") (pintype "passive"))
      (node (ref "R16") (pin "1") (pinfunction "1_1") (pintype "passive"))
    )
    (net (code "131") (name "Net-(Q1-C2)") (class "Default")
      (node (ref "Q1") (pin "4") (pinfunction "C2_4") (pintype "passive"))
      (node (ref "Q2") (pin "4") (pinfunction "G_4") (pintype "bidirectional"))
      (node (ref "R15") (pin "1") (pinfunction "1_1") (pintype "passive"))
    )
    (net (code "132") (name "Net-(Q4A-D-Pad6)") (class "Default")
      (node (ref "Q4") (pin "3") (pinfunction "D_3") (pintype "bidirectional"))
      (node (ref "Q4") (pin "6") (pinfunction "D_6") (pintype "bidirectional"))
      (node (ref "Q4") (pin "EP1") (pinfunction "D_EP1") (pintype "bidirectional"))
      (node (ref "Q4") (pin "EP2") (pinfunction "D_EP2") (pintype "bidirectional"))
    )
    (net (code "133") (name "Net-(Q6-G)") (class "Default")
      (node (ref "Q6") (pin "4") (pinfunction "G_4") (pintype "bidirectional"))
      (node (ref "R45") (pin "2") (pinfunction "2_2") (pintype "passive"))
      (node (ref "S5") (pin "3") (pinfunction "S_3") (pintype "passive"))
    )
    (net (code "134") (name "Net-(Q8-D-Pad1)") (class "Default")
      (node (ref "Q8") (pin "1") (pinfunction "D_1") (pintype "bidirectional"))
      (node (ref "Q8") (pin "2") (pinfunction "D_2") (pintype "bidirectional"))
      (node (ref "Q8") (pin "5") (pinfunction "D_5") (pintype "bidirectional"))
      (node (ref "Q8") (pin "6") (pinfunction "D_6") (pintype "bidirectional"))
      (node (ref "Q8") (pin "EP1") (pinfunction "D_EP1") (pintype "bidirectional"))
      (node (ref "R44") (pin "1") (pinfunction "1_1") (pintype "passive"))
      (node (ref "R47") (pin "1") (pinfunction "1_1") (pintype "passive"))
      (node (ref "R48") (pin "1") (pinfunction "1_1") (pintype "passive"))
      (node (ref "R49") (pin "1") (pinfunction "1_1") (pintype "passive"))
    )
    (net (code "135") (name "Net-(SG1-1)") (class "Default")
      (node (ref "R26") (pin "1") (pinfunction "1_1") (pintype "passive"))
      (node (ref "SG1") (pin "P$1") (pinfunction "1_P$1") (pintype "passive"))
    )
    (net (code "136") (name "VBAT") (class "Default")
      (node (ref "C3") (pin "2") (pinfunction "2_2") (pintype "passive"))
      (node (ref "IC4") (pin "10") (pinfunction "OUT_10") (pintype "passive"))
      (node (ref "JP3") (pin "2") (pinfunction "2_2") (pintype "passive"))
      (node (ref "Q6") (pin "5") (pinfunction "S_5") (pintype "bidirectional"))
      (node (ref "Q6") (pin "6") (pinfunction "S_6") (pintype "bidirectional"))
      (node (ref "Q6") (pin "7") (pinfunction "S_7") (pintype "bidirectional"))
      (node (ref "Q6") (pin "8") (pinfunction "S_8") (pintype "bidirectional"))
      (node (ref "Q6") (pin "EP") (pinfunction "S_EP") (pintype "bidirectional"))
      (node (ref "R21") (pin "2") (pinfunction "2_2") (pintype "passive"))
      (node (ref "R45") (pin "1") (pinfunction "1_1") (pintype "passive"))
      (node (ref "R51") (pin "2") (pinfunction "2_2") (pintype "passive"))
    )
    (net (code "137") (name "unconnected-(IC2-FB-Pad4)") (class "Default")
      (node (ref "IC2") (pin "4") (pinfunction "FB_4") (pintype "input"))
    )
    (net (code "138") (name "unconnected-(IC2-PG-Pad6)") (class "Default")
      (node (ref "IC2") (pin "6") (pinfunction "PG_6") (pintype "bidirectional"))
    )
    (net (code "139") (name "unconnected-(IC4-~{PG}-Pad5)") (class "Default")
      (node (ref "IC4") (pin "5") (pinfunction "~{PG}_5") (pintype "output"))
    )
    (net (code "140") (name "unconnected-(IC6-ANT_SEL_1-Pad25)") (class "Default")
      (node (ref "IC6") (pin "25") (pinfunction "ANT_SEL_1_25") (pintype "output"))
    )
    (net (code "141") (name "unconnected-(IC6-ANT_SEL_2-Pad26)") (class "Default")
      (node (ref "IC6") (pin "26") (pinfunction "ANT_SEL_2_26") (pintype "output"))
    )
    (net (code "142") (name "unconnected-(IC6-SOP0-Pad34)") (class "Default")
      (node (ref "IC6") (pin "34") (pinfunction "SOP0_34") (pintype "bidirectional"))
    )
    (net (code "143") (name "unconnected-(IC6-SOP1-Pad24)") (class "Default")
      (node (ref "IC6") (pin "24") (pinfunction "SOP1_24") (pintype "bidirectional"))
    )
    (net (code "144") (name "unconnected-(IC9-INT-Pad7)") (class "Default")
      (node (ref "IC9") (pin "7") (pinfunction "INT_7") (pintype "output"))
    )
    (net (code "145") (name "unconnected-(J3-KEY-Pad7)") (class "Default")
      (node (ref "J3") (pin "7") (pinfunction "KEY_7") (pintype "bidirectional"))
    )
    (net (code "146") (name "unconnected-(J3-NC-Pad8)") (class "Default")
      (node (ref "J3") (pin "8") (pinfunction "NC_8") (pintype "no_connect"))
    )
    (net (code "147") (name "unconnected-(J3-SWO-Pad6)") (class "Default")
      (node (ref "J3") (pin "6") (pinfunction "SWO_6") (pintype "bidirectional"))
    )
    (net (code "148") (name "unconnected-(JP4-SWO-Pad6)") (class "Default")
      (node (ref "JP4") (pin "6") (pinfunction "SWO_6") (pintype "input"))
    )
    (net (code "149") (name "unconnected-(S5-O-Pad1)") (class "Default")
      (node (ref "S5") (pin "1") (pinfunction "O_1") (pintype "passive"))
    )
  )
)
